# homeboard9.net
KiCad netlist of a schematic drawn in EAGLE
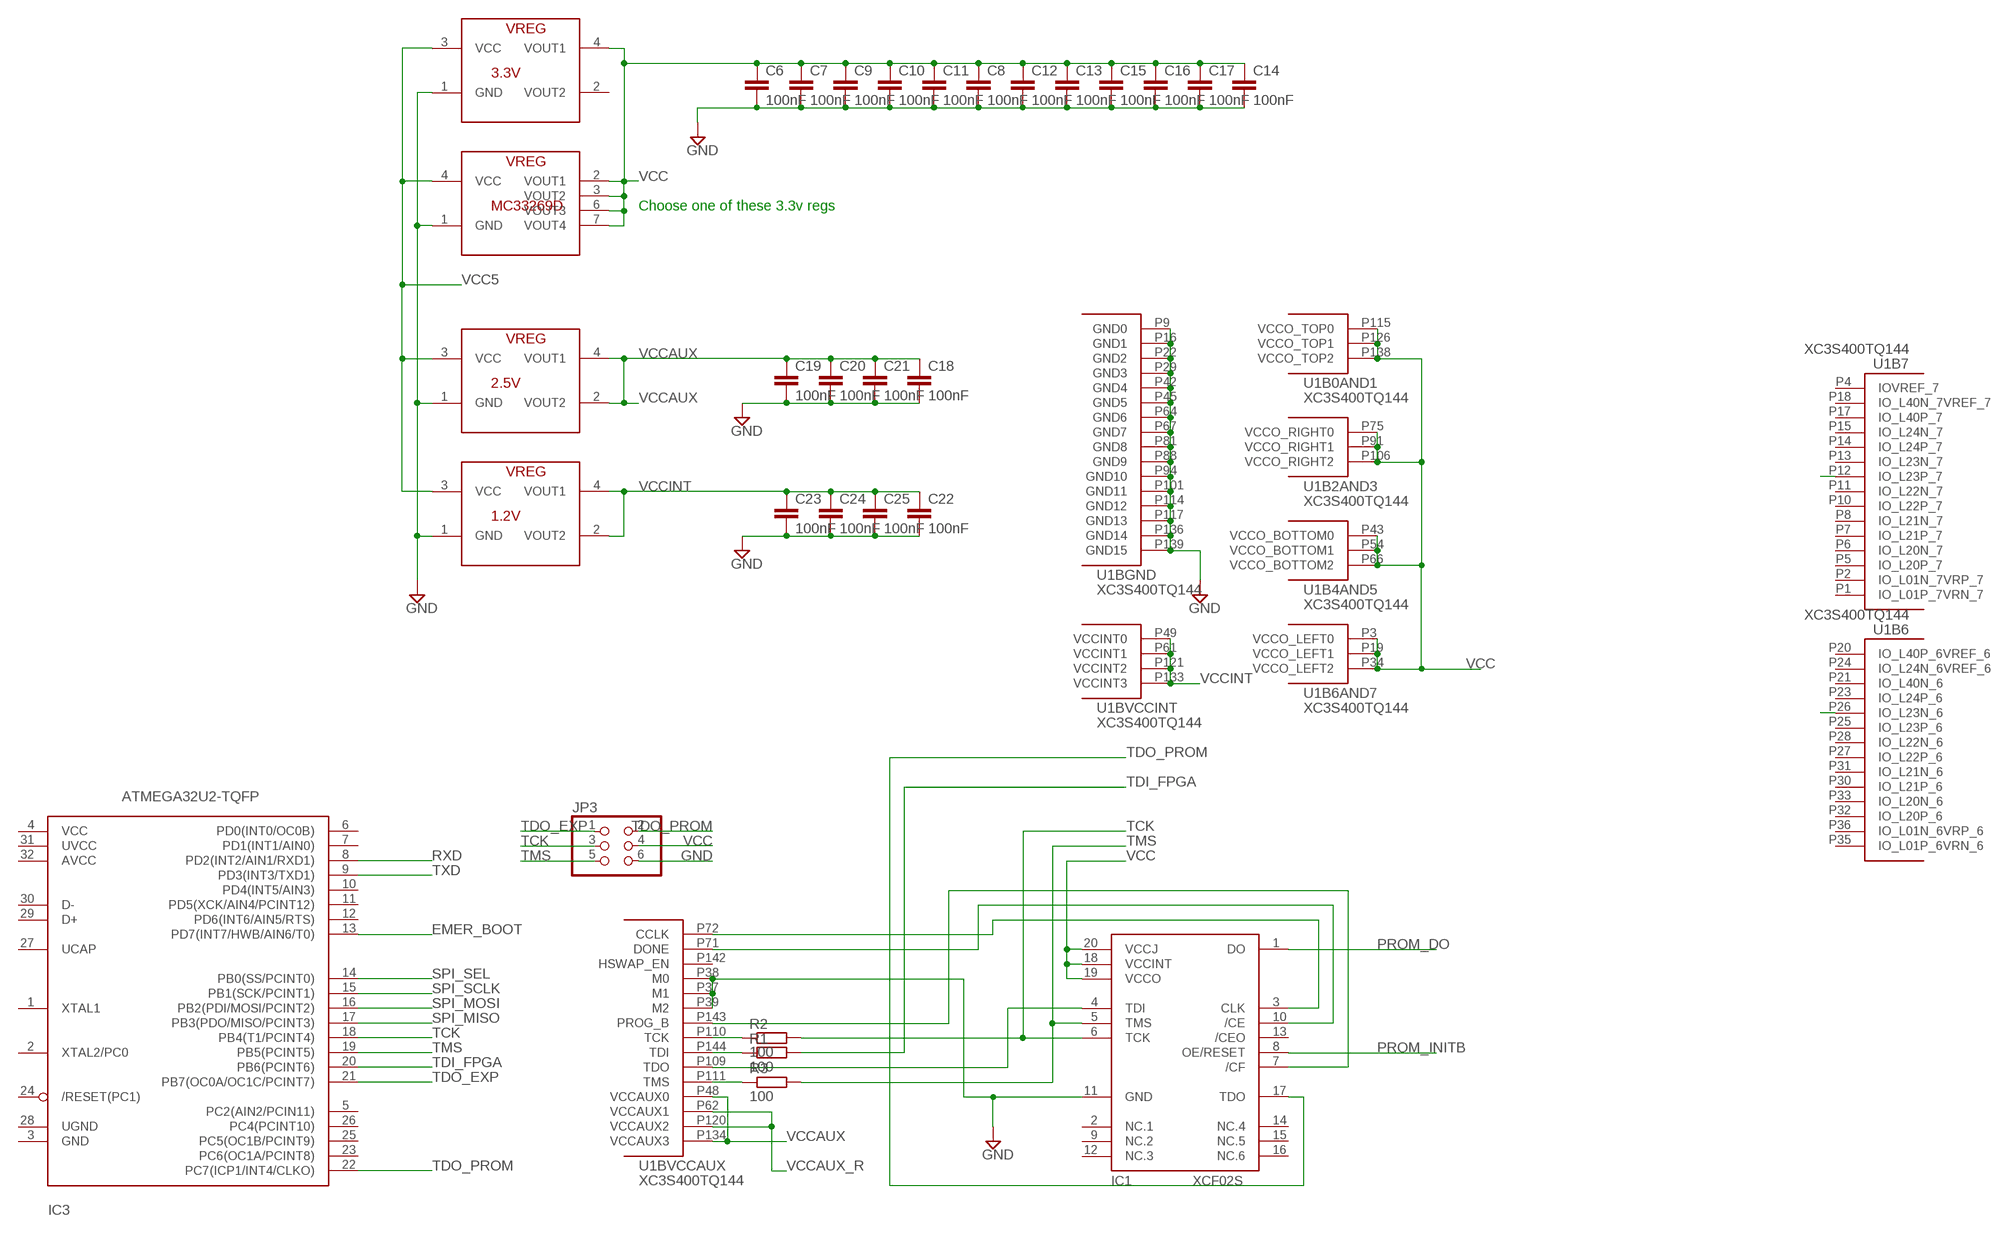
[diagram p0: schematic, sheet 1, part 1 of 3]
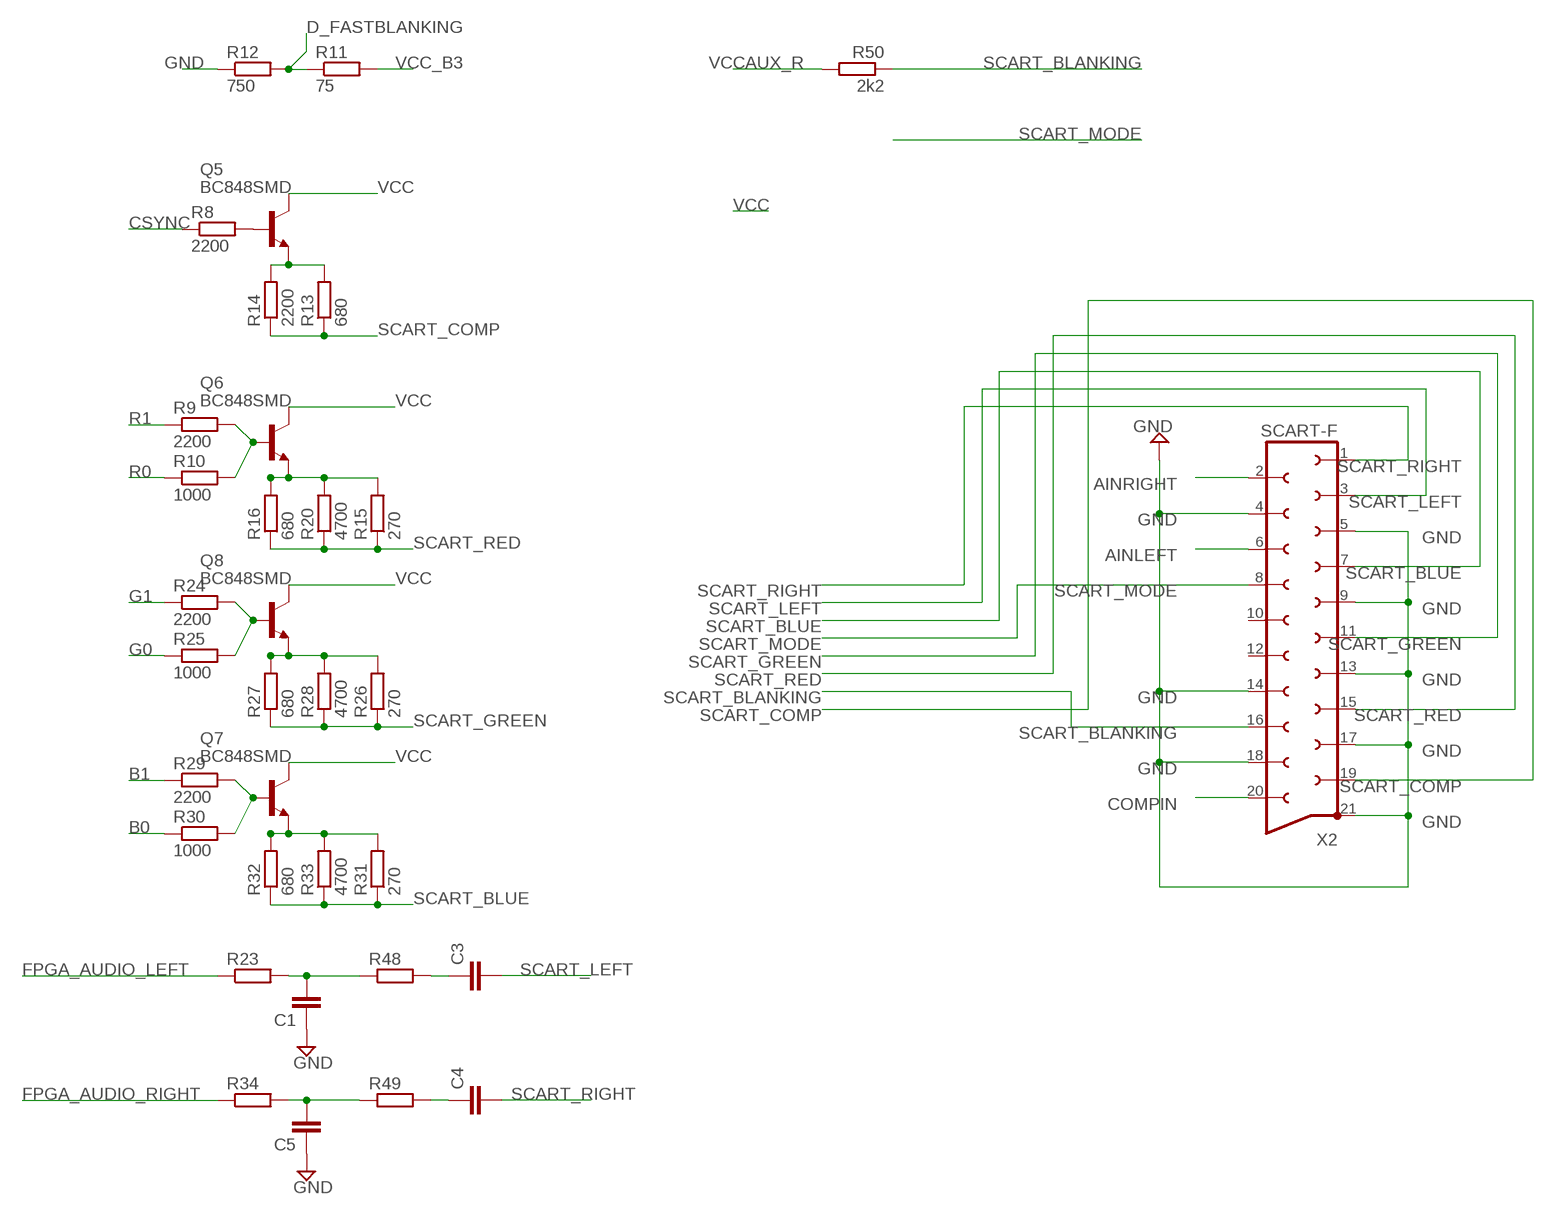
[diagram p1: schematic, sheet 1, part 2 of 3]
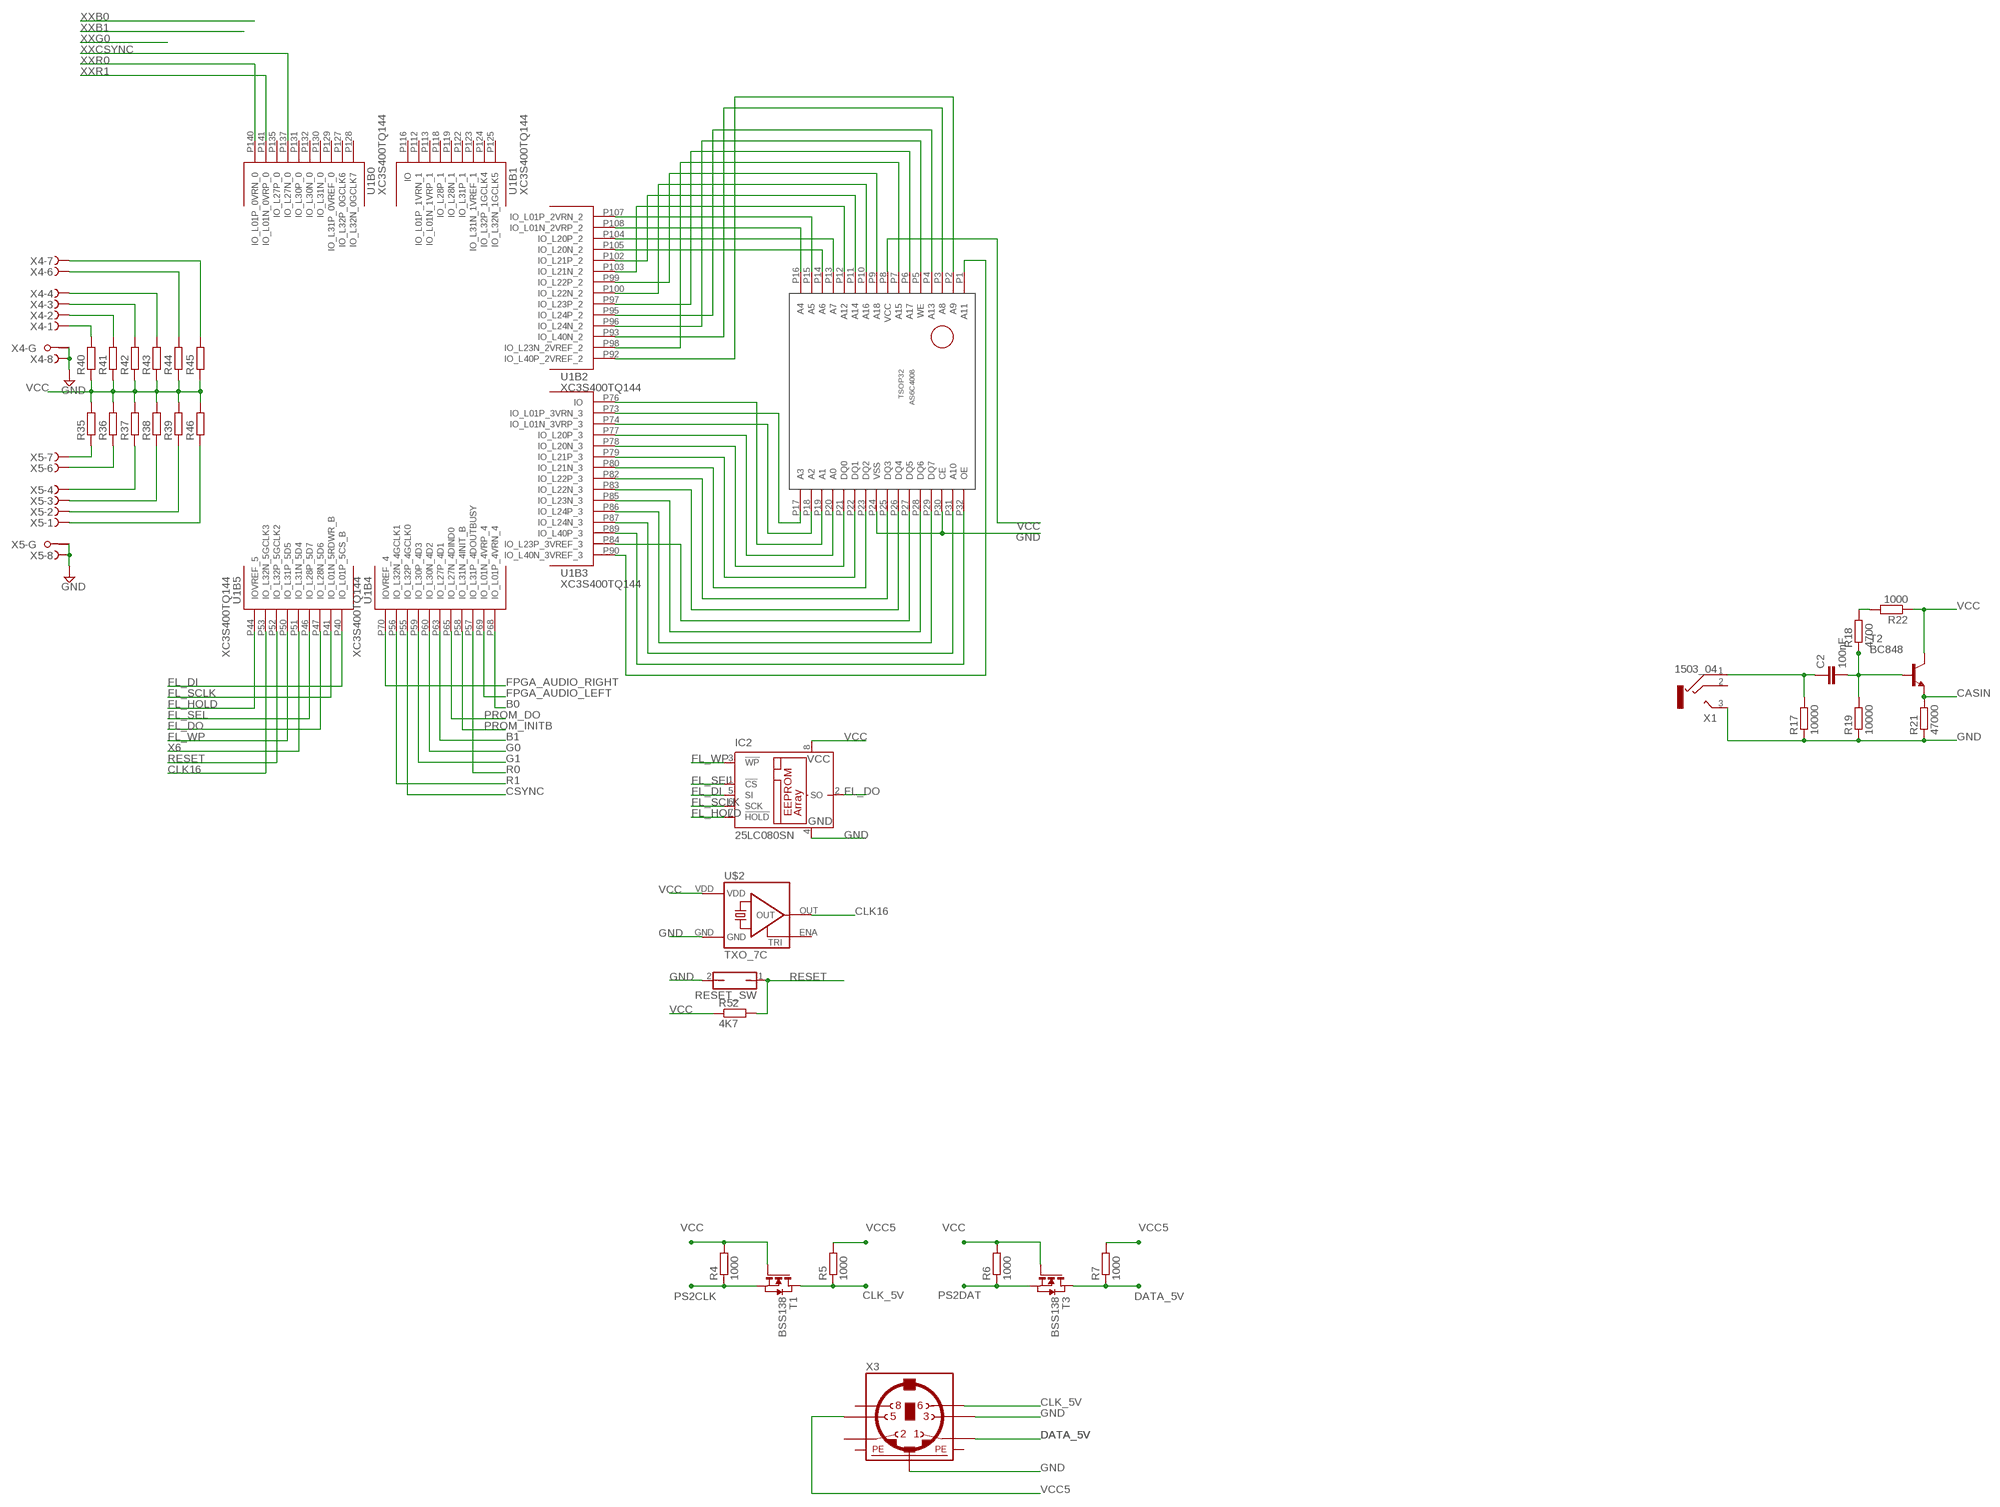
[diagram p2: schematic, sheet 1, part 3 of 3]

(export (version "E")
  (design (tool "Eeschema 10.0.6"))
  (components
    (comp (ref "C1")
      (value "C-EUC0603")
      (footprint "eagle-import:C0603")
      (libsource (lib "eagle-import") (part "resistor_C-EUC0603"))
    )
    (comp (ref "C2")
      (value "100nF")
      (footprint "eagle-import:C0603")
      (libsource (lib "eagle-import") (part "resistor_C-EUC0603"))
    )
    (comp (ref "C3")
      (value "C-EUC0603")
      (footprint "eagle-import:C0603")
      (libsource (lib "eagle-import") (part "resistor_C-EUC0603"))
    )
    (comp (ref "C4")
      (value "C-EUC0603")
      (footprint "eagle-import:C0603")
      (libsource (lib "eagle-import") (part "resistor_C-EUC0603"))
    )
    (comp (ref "C5")
      (value "C-EUC0603")
      (footprint "eagle-import:C0603")
      (libsource (lib "eagle-import") (part "resistor_C-EUC0603"))
    )
    (comp (ref "C6")
      (value "100nF")
      (footprint "eagle-import:C0603")
      (libsource (lib "eagle-import") (part "C-EUC0603"))
    )
    (comp (ref "C7")
      (value "100nF")
      (footprint "eagle-import:C0603")
      (libsource (lib "eagle-import") (part "C-EUC0603"))
    )
    (comp (ref "C8")
      (value "100nF")
      (footprint "eagle-import:C0603")
      (libsource (lib "eagle-import") (part "C-EUC0603"))
    )
    (comp (ref "C9")
      (value "100nF")
      (footprint "eagle-import:C0603")
      (libsource (lib "eagle-import") (part "C-EUC0603"))
    )
    (comp (ref "C10")
      (value "100nF")
      (footprint "eagle-import:C0603")
      (libsource (lib "eagle-import") (part "C-EUC0603"))
    )
    (comp (ref "C11")
      (value "100nF")
      (footprint "eagle-import:C0603")
      (libsource (lib "eagle-import") (part "C-EUC0603"))
    )
    (comp (ref "C12")
      (value "100nF")
      (footprint "eagle-import:C0603")
      (libsource (lib "eagle-import") (part "C-EUC0603"))
    )
    (comp (ref "C13")
      (value "100nF")
      (footprint "eagle-import:C0603")
      (libsource (lib "eagle-import") (part "C-EUC0603"))
    )
    (comp (ref "C14")
      (value "100nF")
      (footprint "eagle-import:C0603")
      (libsource (lib "eagle-import") (part "C-EUC0603"))
    )
    (comp (ref "C15")
      (value "100nF")
      (footprint "eagle-import:C0603")
      (libsource (lib "eagle-import") (part "C-EUC0603"))
    )
    (comp (ref "C16")
      (value "100nF")
      (footprint "eagle-import:C0603")
      (libsource (lib "eagle-import") (part "C-EUC0603"))
    )
    (comp (ref "C17")
      (value "100nF")
      (footprint "eagle-import:C0603")
      (libsource (lib "eagle-import") (part "C-EUC0603"))
    )
    (comp (ref "C18")
      (value "100nF")
      (footprint "eagle-import:C0603")
      (libsource (lib "eagle-import") (part "C-EUC0603"))
    )
    (comp (ref "C19")
      (value "100nF")
      (footprint "eagle-import:C0603")
      (libsource (lib "eagle-import") (part "C-EUC0603"))
    )
    (comp (ref "C20")
      (value "100nF")
      (footprint "eagle-import:C0603")
      (libsource (lib "eagle-import") (part "C-EUC0603"))
    )
    (comp (ref "C21")
      (value "100nF")
      (footprint "eagle-import:C0603")
      (libsource (lib "eagle-import") (part "C-EUC0603"))
    )
    (comp (ref "C22")
      (value "100nF")
      (footprint "eagle-import:C0603")
      (libsource (lib "eagle-import") (part "C-EUC0603"))
    )
    (comp (ref "C23")
      (value "100nF")
      (footprint "eagle-import:C0603")
      (libsource (lib "eagle-import") (part "C-EUC0603"))
    )
    (comp (ref "C24")
      (value "100nF")
      (footprint "eagle-import:C0603")
      (libsource (lib "eagle-import") (part "C-EUC0603"))
    )
    (comp (ref "C25")
      (value "100nF")
      (footprint "eagle-import:C0603")
      (libsource (lib "eagle-import") (part "C-EUC0603"))
    )
    (comp (ref "IC1")
      (value "XCF02S")
      (footprint "eagle-import:VO20")
      (libsource (lib "eagle-import") (part "XCF02S"))
    )
    (comp (ref "IC2")
      (value "25LC080SN")
      (footprint "eagle-import:SO-08")
      (fields (field (name "MF") "MICROCHIP") (field (name "MPN") "25LC080/SN"))
      (libsource (lib "eagle-import") (part "25SNLC080"))
    )
    (comp (ref "IC3")
      (value "ATMEGA32U2-TQFP")
      (footprint "eagle-import:TQFP32-08")
      (libsource (lib "eagle-import") (part "ATMEGA32U2-TQFP"))
    )
    (comp (ref "JP3")
      (value "PINHD-2X3")
      (footprint "eagle-import:2X03")
      (libsource (lib "eagle-import") (part "PINHD-2X3"))
    )
    (comp (ref "Q5")
      (value "BC848SMD")
      (footprint "eagle-import:SOT23")
      (libsource (lib "eagle-import") (part "BC848SMD"))
    )
    (comp (ref "Q6")
      (value "BC848SMD")
      (footprint "eagle-import:SOT23")
      (libsource (lib "eagle-import") (part "BC848SMD"))
    )
    (comp (ref "Q7")
      (value "BC848SMD")
      (footprint "eagle-import:SOT23")
      (libsource (lib "eagle-import") (part "BC848SMD"))
    )
    (comp (ref "Q8")
      (value "BC848SMD")
      (footprint "eagle-import:SOT23")
      (libsource (lib "eagle-import") (part "BC848SMD"))
    )
    (comp (ref "R1")
      (value "100")
      (footprint "eagle-import:R0805")
      (libsource (lib "eagle-import") (part "R-EU_R0805"))
    )
    (comp (ref "R2")
      (value "100")
      (footprint "eagle-import:R0805")
      (libsource (lib "eagle-import") (part "R-EU_R0805"))
    )
    (comp (ref "R3")
      (value "100")
      (footprint "eagle-import:R0805")
      (libsource (lib "eagle-import") (part "R-EU_R0805"))
    )
    (comp (ref "R4")
      (value "1000")
      (footprint "eagle-import:R0805")
      (libsource (lib "eagle-import") (part "R-EU_R0805"))
    )
    (comp (ref "R5")
      (value "1000")
      (footprint "eagle-import:R0805")
      (libsource (lib "eagle-import") (part "R-EU_R0805"))
    )
    (comp (ref "R6")
      (value "1000")
      (footprint "eagle-import:R0805")
      (libsource (lib "eagle-import") (part "R-EU_R0805"))
    )
    (comp (ref "R7")
      (value "1000")
      (footprint "eagle-import:R0805")
      (libsource (lib "eagle-import") (part "R-EU_R0805"))
    )
    (comp (ref "R8")
      (value "2200")
      (footprint "eagle-import:R0805")
      (libsource (lib "eagle-import") (part "R-EU_R0805"))
    )
    (comp (ref "R9")
      (value "2200")
      (footprint "eagle-import:R0805")
      (libsource (lib "eagle-import") (part "R-EU_R0805"))
    )
    (comp (ref "R10")
      (value "1000")
      (footprint "eagle-import:R0805")
      (libsource (lib "eagle-import") (part "R-EU_R0805"))
    )
    (comp (ref "R11")
      (value "75")
      (footprint "eagle-import:R0805")
      (libsource (lib "eagle-import") (part "R-EU_R0805"))
    )
    (comp (ref "R12")
      (value "750")
      (footprint "eagle-import:R0805")
      (libsource (lib "eagle-import") (part "R-EU_R0805"))
    )
    (comp (ref "R13")
      (value "680")
      (footprint "eagle-import:R0805")
      (libsource (lib "eagle-import") (part "R-EU_R0805"))
    )
    (comp (ref "R14")
      (value "2200")
      (footprint "eagle-import:R0805")
      (libsource (lib "eagle-import") (part "R-EU_R0805"))
    )
    (comp (ref "R15")
      (value "270")
      (footprint "eagle-import:R0805")
      (libsource (lib "eagle-import") (part "R-EU_R0805"))
    )
    (comp (ref "R16")
      (value "680")
      (footprint "eagle-import:R0805")
      (libsource (lib "eagle-import") (part "R-EU_R0805"))
    )
    (comp (ref "R17")
      (value "10000")
      (footprint "eagle-import:R0805")
      (libsource (lib "eagle-import") (part "R-EU_R0805"))
    )
    (comp (ref "R18")
      (value "4700")
      (footprint "eagle-import:R0805")
      (libsource (lib "eagle-import") (part "R-EU_R0805"))
    )
    (comp (ref "R19")
      (value "10000")
      (footprint "eagle-import:R0805")
      (libsource (lib "eagle-import") (part "R-EU_R0805"))
    )
    (comp (ref "R20")
      (value "4700")
      (footprint "eagle-import:R0805")
      (libsource (lib "eagle-import") (part "R-EU_R0805"))
    )
    (comp (ref "R21")
      (value "47000")
      (footprint "eagle-import:R0805")
      (libsource (lib "eagle-import") (part "R-EU_R0805"))
    )
    (comp (ref "R22")
      (value "1000")
      (footprint "eagle-import:R0805")
      (libsource (lib "eagle-import") (part "R-EU_R0805"))
    )
    (comp (ref "R23")
      (value "R-EU_M0805")
      (footprint "eagle-import:M0805")
      (libsource (lib "eagle-import") (part "resistor_R-EU_M0805"))
    )
    (comp (ref "R24")
      (value "2200")
      (footprint "eagle-import:R0805")
      (libsource (lib "eagle-import") (part "R-EU_R0805"))
    )
    (comp (ref "R25")
      (value "1000")
      (footprint "eagle-import:R0805")
      (libsource (lib "eagle-import") (part "R-EU_R0805"))
    )
    (comp (ref "R26")
      (value "270")
      (footprint "eagle-import:R0805")
      (libsource (lib "eagle-import") (part "R-EU_R0805"))
    )
    (comp (ref "R27")
      (value "680")
      (footprint "eagle-import:R0805")
      (libsource (lib "eagle-import") (part "R-EU_R0805"))
    )
    (comp (ref "R28")
      (value "4700")
      (footprint "eagle-import:R0805")
      (libsource (lib "eagle-import") (part "R-EU_R0805"))
    )
    (comp (ref "R29")
      (value "2200")
      (footprint "eagle-import:R0805")
      (libsource (lib "eagle-import") (part "R-EU_R0805"))
    )
    (comp (ref "R30")
      (value "1000")
      (footprint "eagle-import:R0805")
      (libsource (lib "eagle-import") (part "R-EU_R0805"))
    )
    (comp (ref "R31")
      (value "270")
      (footprint "eagle-import:R0805")
      (libsource (lib "eagle-import") (part "R-EU_R0805"))
    )
    (comp (ref "R32")
      (value "680")
      (footprint "eagle-import:R0805")
      (libsource (lib "eagle-import") (part "R-EU_R0805"))
    )
    (comp (ref "R33")
      (value "4700")
      (footprint "eagle-import:R0805")
      (libsource (lib "eagle-import") (part "R-EU_R0805"))
    )
    (comp (ref "R34")
      (value "R-EU_M0805")
      (footprint "eagle-import:M0805")
      (libsource (lib "eagle-import") (part "resistor_R-EU_M0805"))
    )
    (comp (ref "R35")
      (value "R-EU_M0805")
      (footprint "eagle-import:M0805")
      (libsource (lib "eagle-import") (part "resistor_R-EU_M0805"))
    )
    (comp (ref "R36")
      (value "R-EU_M0805")
      (footprint "eagle-import:M0805")
      (libsource (lib "eagle-import") (part "resistor_R-EU_M0805"))
    )
    (comp (ref "R37")
      (value "R-EU_M0805")
      (footprint "eagle-import:M0805")
      (libsource (lib "eagle-import") (part "resistor_R-EU_M0805"))
    )
    (comp (ref "R38")
      (value "R-EU_M0805")
      (footprint "eagle-import:M0805")
      (libsource (lib "eagle-import") (part "resistor_R-EU_M0805"))
    )
    (comp (ref "R39")
      (value "R-EU_M0805")
      (footprint "eagle-import:M0805")
      (libsource (lib "eagle-import") (part "resistor_R-EU_M0805"))
    )
    (comp (ref "R40")
      (value "R-EU_M0805")
      (footprint "eagle-import:M0805")
      (libsource (lib "eagle-import") (part "resistor_R-EU_M0805"))
    )
    (comp (ref "R41")
      (value "R-EU_M0805")
      (footprint "eagle-import:M0805")
      (libsource (lib "eagle-import") (part "resistor_R-EU_M0805"))
    )
    (comp (ref "R42")
      (value "R-EU_M0805")
      (footprint "eagle-import:M0805")
      (libsource (lib "eagle-import") (part "resistor_R-EU_M0805"))
    )
    (comp (ref "R43")
      (value "R-EU_M0805")
      (footprint "eagle-import:M0805")
      (libsource (lib "eagle-import") (part "resistor_R-EU_M0805"))
    )
    (comp (ref "R44")
      (value "R-EU_M0805")
      (footprint "eagle-import:M0805")
      (libsource (lib "eagle-import") (part "resistor_R-EU_M0805"))
    )
    (comp (ref "R45")
      (value "R-EU_M0805")
      (footprint "eagle-import:M0805")
      (libsource (lib "eagle-import") (part "resistor_R-EU_M0805"))
    )
    (comp (ref "R46")
      (value "R-EU_M0805")
      (footprint "eagle-import:M0805")
      (libsource (lib "eagle-import") (part "resistor_R-EU_M0805"))
    )
    (comp (ref "R48")
      (value "R-EU_M0805")
      (footprint "eagle-import:M0805")
      (libsource (lib "eagle-import") (part "resistor_R-EU_M0805"))
    )
    (comp (ref "R49")
      (value "R-EU_M0805")
      (footprint "eagle-import:M0805")
      (libsource (lib "eagle-import") (part "resistor_R-EU_M0805"))
    )
    (comp (ref "R50")
      (value "2k2")
      (footprint "eagle-import:M0805")
      (libsource (lib "eagle-import") (part "resistor_R-EU_M0805"))
    )
    (comp (ref "R52")
      (value "4K7")
      (footprint "eagle-import:M0805")
      (libsource (lib "eagle-import") (part "resistor_R-EU_M0805"))
    )
    (comp (ref "REG1.2")
      (value "1.2V")
      (footprint "eagle-import:SOT223")
      (libsource (lib "eagle-import") (part "NX1117"))
    )
    (comp (ref "REG2.5")
      (value "2.5V")
      (footprint "eagle-import:SOT223")
      (libsource (lib "eagle-import") (part "NX1117"))
    )
    (comp (ref "RESET_SW")
      (value "JP1Q")
      (footprint "eagle-import:JP1")
      (libsource (lib "eagle-import") (part "JP1Q"))
    )
    (comp (ref "T1")
      (value "BSS138")
      (footprint "eagle-import:SOT-23")
      (libsource (lib "eagle-import") (part "NMOSSOT23"))
    )
    (comp (ref "T2")
      (value "BC848")
      (footprint "eagle-import:SOT23")
      (libsource (lib "eagle-import") (part "BC848"))
    )
    (comp (ref "T3")
      (value "BSS138")
      (footprint "eagle-import:SOT-23")
      (libsource (lib "eagle-import") (part "NMOSSOT23"))
    )
    (comp (ref "U$1")
      (value "AS6C4008")
      (footprint "eagle-import:TSOP32")
      (libsource (lib "eagle-import") (part "AS6C4008"))
    )
    (comp (ref "U$2")
      (value "TXO_7C")
      (footprint "eagle-import:OSC_7C")
      (libsource (lib "eagle-import") (part "TXO_7C"))
    )
    (comp (ref "U$3")
      (value "MC33269D")
      (footprint "eagle-import:SO8")
      (libsource (lib "eagle-import") (part "MC33269D"))
    )
    (comp (ref "U$4")
      (value "3.3V")
      (footprint "eagle-import:SOT223")
      (libsource (lib "eagle-import") (part "NX1117"))
    )
    (comp (ref "U1")
      (value "XC3S400TQ144")
      (footprint "eagle-import:TQ144")
      (libsource (lib "eagle-import") (part "XC3S400TQ144"))
    )
    (comp (ref "X1")
      (value "1503_04")
      (footprint "eagle-import:1503_04")
      (libsource (lib "eagle-import") (part "1503_04"))
    )
    (comp (ref "X2")
      (value "SCART-F")
      (footprint "eagle-import:SCART-F")
      (libsource (lib "eagle-import") (part "SCART-F"))
    )
    (comp (ref "X3")
      (value "MINI_DIN_6")
      (footprint "eagle-import:M_DIN6")
      (libsource (lib "eagle-import") (part "MINI_DIN_6"))
    )
    (comp (ref "X4")
      (value "F09HPS")
      (footprint "eagle-import:F09HP")
      (libsource (lib "eagle-import") (part "F09HPS"))
    )
    (comp (ref "X5")
      (value "F09HPS")
      (footprint "eagle-import:F09HP")
      (libsource (lib "eagle-import") (part "F09HPS"))
    )
  )
  (nets
    (net (code "1") (name "/AINLEFT") (class "Default")
      (node (ref "X2") (pin "6") (pinfunction "6_6") (pintype "passive"))
    )
    (net (code "2") (name "/AINRIGHT") (class "Default")
      (node (ref "X2") (pin "2") (pinfunction "2_2") (pintype "passive"))
    )
    (net (code "3") (name "/B0") (class "Default")
      (node (ref "R30") (pin "1") (pinfunction "1_1") (pintype "passive"))
      (node (ref "U1") (pin "P68") (pinfunction "IO_L01P_4VRN_4_P68") (pintype "bidirectional"))
    )
    (net (code "4") (name "/B1") (class "Default")
      (node (ref "R29") (pin "1") (pinfunction "1_1") (pintype "passive"))
      (node (ref "U1") (pin "P63") (pinfunction "IO_L27P_4D1_P63") (pintype "bidirectional"))
    )
    (net (code "5") (name "/CASIN") (class "Default")
      (node (ref "R21") (pin "2") (pinfunction "2_2") (pintype "passive"))
      (node (ref "T2") (pin "2") (pinfunction "E_2") (pintype "passive"))
    )
    (net (code "6") (name "/CLK16") (class "Default")
      (node (ref "U$2") (pin "OUT") (pinfunction "OUT_OUT") (pintype "output"))
      (node (ref "U1") (pin "P53") (pinfunction "IO_L32N_5GCLK3_P53") (pintype "bidirectional"))
    )
    (net (code "7") (name "/CLK_5V") (class "Default")
      (node (ref "R5") (pin "1") (pinfunction "1_1") (pintype "passive"))
      (node (ref "T1") (pin "1") (pinfunction "D_1") (pintype "passive"))
      (node (ref "X3") (pin "6") (pinfunction "6_6") (pintype "passive"))
    )
    (net (code "8") (name "/COMPIN") (class "Default")
      (node (ref "X2") (pin "20") (pinfunction "20_20") (pintype "passive"))
    )
    (net (code "9") (name "/CSYNC") (class "Default")
      (node (ref "R8") (pin "1") (pinfunction "1_1") (pintype "passive"))
      (node (ref "U1") (pin "P55") (pinfunction "IO_L32P_4GCLK0_P55") (pintype "bidirectional"))
    )
    (net (code "10") (name "/DATA_5V") (class "Default")
      (node (ref "R7") (pin "1") (pinfunction "1_1") (pintype "passive"))
      (node (ref "T3") (pin "1") (pinfunction "D_1") (pintype "passive"))
      (node (ref "X3") (pin "1") (pinfunction "1_1") (pintype "passive"))
    )
    (net (code "11") (name "/D_FASTBLANKING") (class "Default")
      (node (ref "R11") (pin "1") (pinfunction "1_1") (pintype "passive"))
      (node (ref "R12") (pin "2") (pinfunction "2_2") (pintype "passive"))
    )
    (net (code "12") (name "/EMER_BOOT") (class "Default")
      (node (ref "IC3") (pin "13") (pinfunction "PD7(INT7/HWB/AIN6/T0)_13") (pintype "bidirectional"))
    )
    (net (code "13") (name "/FL_DI") (class "Default")
      (node (ref "IC2") (pin "5") (pinfunction "SI_5") (pintype "input"))
      (node (ref "U1") (pin "P40") (pinfunction "IO_L01P_5CS_B_P40") (pintype "bidirectional"))
    )
    (net (code "14") (name "/FL_DO") (class "Default")
      (node (ref "IC2") (pin "2") (pinfunction "SO_2") (pintype "bidirectional"))
      (node (ref "U1") (pin "P47") (pinfunction "IO_L28N_5D6_P47") (pintype "bidirectional"))
    )
    (net (code "15") (name "/FL_HOLD") (class "Default")
      (node (ref "IC2") (pin "7") (pinfunction "~{HOLD}_7") (pintype "input"))
      (node (ref "U1") (pin "P44") (pinfunction "IOVREF_5_P44") (pintype "bidirectional"))
    )
    (net (code "16") (name "/FL_SCLK") (class "Default")
      (node (ref "IC2") (pin "6") (pinfunction "SCK_6") (pintype "input"))
      (node (ref "U1") (pin "P41") (pinfunction "IO_L01N_5RDWR_B_P41") (pintype "bidirectional"))
    )
    (net (code "17") (name "/FL_SEL") (class "Default")
      (node (ref "IC2") (pin "1") (pinfunction "~{CS}_1") (pintype "input"))
      (node (ref "U1") (pin "P46") (pinfunction "IO_L28P_5D7_P46") (pintype "bidirectional"))
    )
    (net (code "18") (name "/FL_WP") (class "Default")
      (node (ref "IC2") (pin "3") (pinfunction "~{WP}_3") (pintype "input"))
      (node (ref "U1") (pin "P50") (pinfunction "IO_L31P_5D5_P50") (pintype "bidirectional"))
    )
    (net (code "19") (name "/FPGA_AUDIO_LEFT") (class "Default")
      (node (ref "R23") (pin "1") (pinfunction "1_1") (pintype "passive"))
      (node (ref "U1") (pin "P69") (pinfunction "IO_L01N_4VRP_4_P69") (pintype "bidirectional"))
    )
    (net (code "20") (name "/FPGA_AUDIO_RIGHT") (class "Default")
      (node (ref "R34") (pin "1") (pinfunction "1_1") (pintype "passive"))
      (node (ref "U1") (pin "P70") (pinfunction "IOVREF_4_P70") (pintype "bidirectional"))
    )
    (net (code "21") (name "/G0") (class "Default")
      (node (ref "R25") (pin "1") (pinfunction "1_1") (pintype "passive"))
      (node (ref "U1") (pin "P60") (pinfunction "IO_L30N_4D2_P60") (pintype "bidirectional"))
    )
    (net (code "22") (name "/G1") (class "Default")
      (node (ref "R24") (pin "1") (pinfunction "1_1") (pintype "passive"))
      (node (ref "U1") (pin "P59") (pinfunction "IO_L30P_4D3_P59") (pintype "bidirectional"))
    )
    (net (code "23") (name "/PE1") (class "Default")
      (node (ref "X3") (pin "SH1") (pinfunction "PE1_SH1") (pintype "power_in"))
    )
    (net (code "24") (name "/PE3") (class "Default")
      (node (ref "X3") (pin "SH3") (pinfunction "PE3_SH3") (pintype "power_in"))
    )
    (net (code "25") (name "/PROM_DO") (class "Default")
      (node (ref "IC1") (pin "1") (pinfunction "DO_1") (pintype "bidirectional"))
      (node (ref "U1") (pin "P65") (pinfunction "IO_L27N_4DIND0_P65") (pintype "bidirectional"))
    )
    (net (code "26") (name "/PROM_INITB") (class "Default")
      (node (ref "IC1") (pin "8") (pinfunction "OE/RESET_8") (pintype "bidirectional"))
      (node (ref "U1") (pin "P58") (pinfunction "IO_L31N_4INIT_B_P58") (pintype "bidirectional"))
    )
    (net (code "27") (name "/PS2CLK") (class "Default")
      (node (ref "R4") (pin "1") (pinfunction "1_1") (pintype "passive"))
      (node (ref "T1") (pin "2") (pinfunction "S_2") (pintype "passive"))
    )
    (net (code "28") (name "/PS2DAT") (class "Default")
      (node (ref "R6") (pin "1") (pinfunction "1_1") (pintype "passive"))
      (node (ref "T3") (pin "2") (pinfunction "S_2") (pintype "passive"))
    )
    (net (code "29") (name "/R0") (class "Default")
      (node (ref "R10") (pin "1") (pinfunction "1_1") (pintype "passive"))
      (node (ref "U1") (pin "P57") (pinfunction "IO_L31P_4DOUTBUSY_P57") (pintype "bidirectional"))
    )
    (net (code "30") (name "/R1") (class "Default")
      (node (ref "R9") (pin "1") (pinfunction "1_1") (pintype "passive"))
      (node (ref "U1") (pin "P56") (pinfunction "IO_L32N_4GCLK1_P56") (pintype "bidirectional"))
    )
    (net (code "31") (name "/RESET") (class "Default")
      (node (ref "R52") (pin "2") (pinfunction "2_2") (pintype "passive"))
      (node (ref "RESET_SW") (pin "1") (pinfunction "1_1") (pintype "passive"))
      (node (ref "U1") (pin "P52") (pinfunction "IO_L32P_5GCLK2_P52") (pintype "bidirectional"))
    )
    (net (code "32") (name "/RXD") (class "Default")
      (node (ref "IC3") (pin "8") (pinfunction "PD2(INT2/AIN1/RXD1)_8") (pintype "bidirectional"))
    )
    (net (code "33") (name "/SCART_BLANKING") (class "Default")
      (node (ref "R50") (pin "1") (pinfunction "1_1") (pintype "passive"))
      (node (ref "X2") (pin "16") (pinfunction "16_16") (pintype "passive"))
    )
    (net (code "34") (name "/SCART_BLUE") (class "Default")
      (node (ref "R31") (pin "1") (pinfunction "1_1") (pintype "passive"))
      (node (ref "R32") (pin "1") (pinfunction "1_1") (pintype "passive"))
      (node (ref "R33") (pin "1") (pinfunction "1_1") (pintype "passive"))
      (node (ref "X2") (pin "7") (pinfunction "7_7") (pintype "passive"))
    )
    (net (code "35") (name "/SCART_COMP") (class "Default")
      (node (ref "R13") (pin "1") (pinfunction "1_1") (pintype "passive"))
      (node (ref "R14") (pin "1") (pinfunction "1_1") (pintype "passive"))
      (node (ref "X2") (pin "19") (pinfunction "19_19") (pintype "passive"))
    )
    (net (code "36") (name "/SCART_GREEN") (class "Default")
      (node (ref "R26") (pin "1") (pinfunction "1_1") (pintype "passive"))
      (node (ref "R27") (pin "1") (pinfunction "1_1") (pintype "passive"))
      (node (ref "R28") (pin "1") (pinfunction "1_1") (pintype "passive"))
      (node (ref "X2") (pin "11") (pinfunction "11_11") (pintype "passive"))
    )
    (net (code "37") (name "/SCART_LEFT") (class "Default")
      (node (ref "C3") (pin "2") (pinfunction "2_2") (pintype "passive"))
      (node (ref "X2") (pin "3") (pinfunction "3_3") (pintype "passive"))
    )
    (net (code "38") (name "/SCART_MODE") (class "Default")
      (node (ref "X2") (pin "8") (pinfunction "8_8") (pintype "passive"))
    )
    (net (code "39") (name "/SCART_RED") (class "Default")
      (node (ref "R15") (pin "1") (pinfunction "1_1") (pintype "passive"))
      (node (ref "R16") (pin "1") (pinfunction "1_1") (pintype "passive"))
      (node (ref "R20") (pin "1") (pinfunction "1_1") (pintype "passive"))
      (node (ref "X2") (pin "15") (pinfunction "15_15") (pintype "passive"))
    )
    (net (code "40") (name "/SCART_RIGHT") (class "Default")
      (node (ref "C4") (pin "2") (pinfunction "2_2") (pintype "passive"))
      (node (ref "X2") (pin "1") (pinfunction "1_1") (pintype "passive"))
    )
    (net (code "41") (name "/SPI_MISO") (class "Default")
      (node (ref "IC3") (pin "17") (pinfunction "PB3(PDO/MISO/PCINT3)_17") (pintype "bidirectional"))
    )
    (net (code "42") (name "/SPI_MOSI") (class "Default")
      (node (ref "IC3") (pin "16") (pinfunction "PB2(PDI/MOSI/PCINT2)_16") (pintype "bidirectional"))
    )
    (net (code "43") (name "/SPI_SCLK") (class "Default")
      (node (ref "IC3") (pin "15") (pinfunction "PB1(SCK/PCINT1)_15") (pintype "bidirectional"))
    )
    (net (code "44") (name "/SPI_SEL") (class "Default")
      (node (ref "IC3") (pin "14") (pinfunction "PB0(SS/PCINT0)_14") (pintype "bidirectional"))
    )
    (net (code "45") (name "/TCK") (class "Default")
      (node (ref "IC1") (pin "6") (pinfunction "TCK_6") (pintype "bidirectional"))
      (node (ref "IC3") (pin "18") (pinfunction "PB4(T1/PCINT4)_18") (pintype "bidirectional"))
      (node (ref "JP3") (pin "3") (pinfunction "3_3") (pintype "passive"))
      (node (ref "R2") (pin "2") (pinfunction "2_2") (pintype "passive"))
    )
    (net (code "46") (name "/TDI_FPGA") (class "Default")
      (node (ref "IC3") (pin "20") (pinfunction "PB6(PCINT6)_20") (pintype "bidirectional"))
      (node (ref "R1") (pin "2") (pinfunction "2_2") (pintype "passive"))
    )
    (net (code "47") (name "/TDO_EXP") (class "Default")
      (node (ref "IC3") (pin "21") (pinfunction "PB7(OC0A/OC1C/PCINT7)_21") (pintype "bidirectional"))
      (node (ref "JP3") (pin "1") (pinfunction "1_1") (pintype "passive"))
    )
    (net (code "48") (name "/TDO_PROM") (class "Default")
      (node (ref "IC1") (pin "17") (pinfunction "TDO_17") (pintype "bidirectional"))
      (node (ref "IC3") (pin "22") (pinfunction "PC7(ICP1/INT4/CLKO)_22") (pintype "bidirectional"))
      (node (ref "JP3") (pin "2") (pinfunction "2_2") (pintype "passive"))
    )
    (net (code "49") (name "/TMS") (class "Default")
      (node (ref "IC1") (pin "5") (pinfunction "TMS_5") (pintype "bidirectional"))
      (node (ref "IC3") (pin "19") (pinfunction "PB5(PCINT5)_19") (pintype "bidirectional"))
      (node (ref "JP3") (pin "5") (pinfunction "5_5") (pintype "passive"))
      (node (ref "R3") (pin "2") (pinfunction "2_2") (pintype "passive"))
    )
    (net (code "50") (name "/TXD") (class "Default")
      (node (ref "IC3") (pin "9") (pinfunction "PD3(INT3/TXD1)_9") (pintype "bidirectional"))
    )
    (net (code "51") (name "/VCC") (class "Default")
      (node (ref "C10") (pin "1") (pinfunction "1_1") (pintype "passive"))
      (node (ref "C11") (pin "1") (pinfunction "1_1") (pintype "passive"))
      (node (ref "C12") (pin "1") (pinfunction "1_1") (pintype "passive"))
      (node (ref "C13") (pin "1") (pinfunction "1_1") (pintype "passive"))
      (node (ref "C14") (pin "1") (pinfunction "1_1") (pintype "passive"))
      (node (ref "C15") (pin "1") (pinfunction "1_1") (pintype "passive"))
      (node (ref "C16") (pin "1") (pinfunction "1_1") (pintype "passive"))
      (node (ref "C17") (pin "1") (pinfunction "1_1") (pintype "passive"))
      (node (ref "C6") (pin "1") (pinfunction "1_1") (pintype "passive"))
      (node (ref "C7") (pin "1") (pinfunction "1_1") (pintype "passive"))
      (node (ref "C8") (pin "1") (pinfunction "1_1") (pintype "passive"))
      (node (ref "C9") (pin "1") (pinfunction "1_1") (pintype "passive"))
      (node (ref "IC1") (pin "18") (pinfunction "VCCINT_18") (pintype "bidirectional"))
      (node (ref "IC1") (pin "19") (pinfunction "VCCO_19") (pintype "bidirectional"))
      (node (ref "IC1") (pin "20") (pinfunction "VCCJ_20") (pintype "bidirectional"))
      (node (ref "IC2") (pin "8") (pinfunction "VCC_8") (pintype "power_in"))
      (node (ref "JP3") (pin "4") (pinfunction "4_4") (pintype "passive"))
      (node (ref "Q5") (pin "3") (pinfunction "C_3") (pintype "passive"))
      (node (ref "Q6") (pin "3") (pinfunction "C_3") (pintype "passive"))
      (node (ref "Q7") (pin "3") (pinfunction "C_3") (pintype "passive"))
      (node (ref "Q8") (pin "3") (pinfunction "C_3") (pintype "passive"))
      (node (ref "R22") (pin "1") (pinfunction "1_1") (pintype "passive"))
      (node (ref "R35") (pin "2") (pinfunction "2_2") (pintype "passive"))
      (node (ref "R36") (pin "2") (pinfunction "2_2") (pintype "passive"))
      (node (ref "R37") (pin "2") (pinfunction "2_2") (pintype "passive"))
      (node (ref "R38") (pin "2") (pinfunction "2_2") (pintype "passive"))
      (node (ref "R39") (pin "2") (pinfunction "2_2") (pintype "passive"))
      (node (ref "R4") (pin "2") (pinfunction "2_2") (pintype "passive"))
      (node (ref "R40") (pin "1") (pinfunction "1_1") (pintype "passive"))
      (node (ref "R41") (pin "1") (pinfunction "1_1") (pintype "passive"))
      (node (ref "R42") (pin "1") (pinfunction "1_1") (pintype "passive"))
      (node (ref "R43") (pin "1") (pinfunction "1_1") (pintype "passive"))
      (node (ref "R44") (pin "1") (pinfunction "1_1") (pintype "passive"))
      (node (ref "R45") (pin "1") (pinfunction "1_1") (pintype "passive"))
      (node (ref "R46") (pin "2") (pinfunction "2_2") (pintype "passive"))
      (node (ref "R52") (pin "1") (pinfunction "1_1") (pintype "passive"))
      (node (ref "R6") (pin "2") (pinfunction "2_2") (pintype "passive"))
      (node (ref "T1") (pin "3") (pinfunction "G_3") (pintype "passive"))
      (node (ref "T2") (pin "3") (pinfunction "C_3") (pintype "passive"))
      (node (ref "T3") (pin "3") (pinfunction "G_3") (pintype "passive"))
      (node (ref "U$1") (pin "P8") (pinfunction "VCC_P8") (pintype "bidirectional"))
      (node (ref "U$2") (pin "VDD") (pinfunction "VDD_VDD") (pintype "power_in"))
      (node (ref "U$3") (pin "2") (pinfunction "VOUT1_2") (pintype "output"))
      (node (ref "U$3") (pin "3") (pinfunction "VOUT2_3") (pintype "output"))
      (node (ref "U$3") (pin "6") (pinfunction "VOUT3_6") (pintype "output"))
      (node (ref "U$3") (pin "7") (pinfunction "VOUT4_7") (pintype "output"))
      (node (ref "U$4") (pin "4") (pinfunction "VOUT1_4") (pintype "bidirectional"))
      (node (ref "U1") (pin "P106") (pinfunction "VCCO_RIGHT2_P106") (pintype "passive"))
      (node (ref "U1") (pin "P115") (pinfunction "VCCO_TOP0_P115") (pintype "passive"))
      (node (ref "U1") (pin "P126") (pinfunction "VCCO_TOP1_P126") (pintype "passive"))
      (node (ref "U1") (pin "P138") (pinfunction "VCCO_TOP2_P138") (pintype "passive"))
      (node (ref "U1") (pin "P19") (pinfunction "VCCO_LEFT1_P19") (pintype "passive"))
      (node (ref "U1") (pin "P3") (pinfunction "VCCO_LEFT0_P3") (pintype "passive"))
      (node (ref "U1") (pin "P34") (pinfunction "VCCO_LEFT2_P34") (pintype "passive"))
      (node (ref "U1") (pin "P43") (pinfunction "VCCO_BOTTOM0_P43") (pintype "passive"))
      (node (ref "U1") (pin "P54") (pinfunction "VCCO_BOTTOM1_P54") (pintype "passive"))
      (node (ref "U1") (pin "P66") (pinfunction "VCCO_BOTTOM2_P66") (pintype "passive"))
      (node (ref "U1") (pin "P75") (pinfunction "VCCO_RIGHT0_P75") (pintype "passive"))
      (node (ref "U1") (pin "P91") (pinfunction "VCCO_RIGHT1_P91") (pintype "passive"))
    )
    (net (code "52") (name "/VCC5") (class "Default")
      (node (ref "R5") (pin "2") (pinfunction "2_2") (pintype "passive"))
      (node (ref "R7") (pin "2") (pinfunction "2_2") (pintype "passive"))
      (node (ref "REG1.2") (pin "3") (pinfunction "VCC_3") (pintype "bidirectional"))
      (node (ref "REG2.5") (pin "3") (pinfunction "VCC_3") (pintype "bidirectional"))
      (node (ref "U$3") (pin "4") (pinfunction "VCC_4") (pintype "bidirectional"))
      (node (ref "U$4") (pin "3") (pinfunction "VCC_3") (pintype "bidirectional"))
      (node (ref "X3") (pin "5") (pinfunction "5_5") (pintype "passive"))
    )
    (net (code "53") (name "/VCCAUX") (class "Default")
      (node (ref "C18") (pin "1") (pinfunction "1_1") (pintype "passive"))
      (node (ref "C19") (pin "1") (pinfunction "1_1") (pintype "passive"))
      (node (ref "C20") (pin "1") (pinfunction "1_1") (pintype "passive"))
      (node (ref "C21") (pin "1") (pinfunction "1_1") (pintype "passive"))
      (node (ref "REG2.5") (pin "2") (pinfunction "VOUT2_2") (pintype "bidirectional"))
      (node (ref "REG2.5") (pin "4") (pinfunction "VOUT1_4") (pintype "bidirectional"))
      (node (ref "U1") (pin "P134") (pinfunction "VCCAUX3_P134") (pintype "passive"))
      (node (ref "U1") (pin "P48") (pinfunction "VCCAUX0_P48") (pintype "passive"))
    )
    (net (code "54") (name "/VCCAUX_R") (class "Default")
      (node (ref "R50") (pin "2") (pinfunction "2_2") (pintype "passive"))
      (node (ref "U1") (pin "P120") (pinfunction "VCCAUX2_P120") (pintype "passive"))
      (node (ref "U1") (pin "P62") (pinfunction "VCCAUX1_P62") (pintype "passive"))
    )
    (net (code "55") (name "/VCCINT") (class "Default")
      (node (ref "C22") (pin "1") (pinfunction "1_1") (pintype "passive"))
      (node (ref "C23") (pin "1") (pinfunction "1_1") (pintype "passive"))
      (node (ref "C24") (pin "1") (pinfunction "1_1") (pintype "passive"))
      (node (ref "C25") (pin "1") (pinfunction "1_1") (pintype "passive"))
      (node (ref "REG1.2") (pin "2") (pinfunction "VOUT2_2") (pintype "bidirectional"))
      (node (ref "REG1.2") (pin "4") (pinfunction "VOUT1_4") (pintype "bidirectional"))
      (node (ref "U1") (pin "P121") (pinfunction "VCCINT2_P121") (pintype "passive"))
      (node (ref "U1") (pin "P133") (pinfunction "VCCINT3_P133") (pintype "passive"))
      (node (ref "U1") (pin "P49") (pinfunction "VCCINT0_P49") (pintype "passive"))
      (node (ref "U1") (pin "P61") (pinfunction "VCCINT1_P61") (pintype "passive"))
    )
    (net (code "56") (name "/VCC_B3") (class "Default")
      (node (ref "R11") (pin "2") (pinfunction "2_2") (pintype "passive"))
    )
    (net (code "57") (name "/X6") (class "Default")
      (node (ref "U1") (pin "P51") (pinfunction "IO_L31N_5D4_P51") (pintype "bidirectional"))
    )
    (net (code "60") (name "/XXCSYNC") (class "Default")
      (node (ref "U1") (pin "P137") (pinfunction "IO_L27N_0_P137") (pintype "bidirectional"))
    )
    (net (code "62") (name "/XXR0") (class "Default")
      (node (ref "U1") (pin "P140") (pinfunction "IO_L01P_0VRN_0_P140") (pintype "bidirectional"))
    )
    (net (code "63") (name "/XXR1") (class "Default")
      (node (ref "U1") (pin "P141") (pinfunction "IO_L01N_0VRP_0_P141") (pintype "bidirectional"))
    )
    (net (code "64") (name "GND") (class "Default")
      (node (ref "C1") (pin "1") (pinfunction "1_1") (pintype "passive"))
      (node (ref "C10") (pin "2") (pinfunction "2_2") (pintype "passive"))
      (node (ref "C11") (pin "2") (pinfunction "2_2") (pintype "passive"))
      (node (ref "C12") (pin "2") (pinfunction "2_2") (pintype "passive"))
      (node (ref "C13") (pin "2") (pinfunction "2_2") (pintype "passive"))
      (node (ref "C14") (pin "2") (pinfunction "2_2") (pintype "passive"))
      (node (ref "C15") (pin "2") (pinfunction "2_2") (pintype "passive"))
      (node (ref "C16") (pin "2") (pinfunction "2_2") (pintype "passive"))
      (node (ref "C17") (pin "2") (pinfunction "2_2") (pintype "passive"))
      (node (ref "C18") (pin "2") (pinfunction "2_2") (pintype "passive"))
      (node (ref "C19") (pin "2") (pinfunction "2_2") (pintype "passive"))
      (node (ref "C20") (pin "2") (pinfunction "2_2") (pintype "passive"))
      (node (ref "C21") (pin "2") (pinfunction "2_2") (pintype "passive"))
      (node (ref "C22") (pin "2") (pinfunction "2_2") (pintype "passive"))
      (node (ref "C23") (pin "2") (pinfunction "2_2") (pintype "passive"))
      (node (ref "C24") (pin "2") (pinfunction "2_2") (pintype "passive"))
      (node (ref "C25") (pin "2") (pinfunction "2_2") (pintype "passive"))
      (node (ref "C5") (pin "1") (pinfunction "1_1") (pintype "passive"))
      (node (ref "C6") (pin "2") (pinfunction "2_2") (pintype "passive"))
      (node (ref "C7") (pin "2") (pinfunction "2_2") (pintype "passive"))
      (node (ref "C8") (pin "2") (pinfunction "2_2") (pintype "passive"))
      (node (ref "C9") (pin "2") (pinfunction "2_2") (pintype "passive"))
      (node (ref "IC1") (pin "11") (pinfunction "GND_11") (pintype "bidirectional"))
      (node (ref "IC2") (pin "4") (pinfunction "GND_4") (pintype "power_in"))
      (node (ref "JP3") (pin "6") (pinfunction "6_6") (pintype "passive"))
      (node (ref "R12") (pin "1") (pinfunction "1_1") (pintype "passive"))
      (node (ref "R17") (pin "1") (pinfunction "1_1") (pintype "passive"))
      (node (ref "R19") (pin "1") (pinfunction "1_1") (pintype "passive"))
      (node (ref "R21") (pin "1") (pinfunction "1_1") (pintype "passive"))
      (node (ref "REG1.2") (pin "1") (pinfunction "GND_1") (pintype "bidirectional"))
      (node (ref "REG2.5") (pin "1") (pinfunction "GND_1") (pintype "bidirectional"))
      (node (ref "RESET_SW") (pin "2") (pinfunction "2_2") (pintype "passive"))
      (node (ref "U$1") (pin "P24") (pinfunction "VSS_P24") (pintype "bidirectional"))
      (node (ref "U$1") (pin "P30") (pinfunction "CE_P30") (pintype "bidirectional"))
      (node (ref "U$2") (pin "GND") (pinfunction "GND_GND") (pintype "power_in"))
      (node (ref "U$3") (pin "1") (pinfunction "GND_1") (pintype "bidirectional"))
      (node (ref "U$4") (pin "1") (pinfunction "GND_1") (pintype "bidirectional"))
      (node (ref "U1") (pin "P101") (pinfunction "GND11_P101") (pintype "passive"))
      (node (ref "U1") (pin "P114") (pinfunction "GND12_P114") (pintype "passive"))
      (node (ref "U1") (pin "P117") (pinfunction "GND13_P117") (pintype "passive"))
      (node (ref "U1") (pin "P136") (pinfunction "GND14_P136") (pintype "passive"))
      (node (ref "U1") (pin "P139") (pinfunction "GND15_P139") (pintype "passive"))
      (node (ref "U1") (pin "P16") (pinfunction "GND1_P16") (pintype "passive"))
      (node (ref "U1") (pin "P22") (pinfunction "GND2_P22") (pintype "passive"))
      (node (ref "U1") (pin "P29") (pinfunction "GND3_P29") (pintype "passive"))
      (node (ref "U1") (pin "P37") (pinfunction "M1_P37") (pintype "bidirectional"))
      (node (ref "U1") (pin "P38") (pinfunction "M0_P38") (pintype "bidirectional"))
      (node (ref "U1") (pin "P39") (pinfunction "M2_P39") (pintype "bidirectional"))
      (node (ref "U1") (pin "P42") (pinfunction "GND4_P42") (pintype "passive"))
      (node (ref "U1") (pin "P45") (pinfunction "GND5_P45") (pintype "passive"))
      (node (ref "U1") (pin "P64") (pinfunction "GND6_P64") (pintype "passive"))
      (node (ref "U1") (pin "P67") (pinfunction "GND7_P67") (pintype "passive"))
      (node (ref "U1") (pin "P81") (pinfunction "GND8_P81") (pintype "passive"))
      (node (ref "U1") (pin "P88") (pinfunction "GND9_P88") (pintype "passive"))
      (node (ref "U1") (pin "P9") (pinfunction "GND0_P9") (pintype "passive"))
      (node (ref "U1") (pin "P94") (pinfunction "GND10_P94") (pintype "passive"))
      (node (ref "X1") (pin "3") (pinfunction "2_3") (pintype "passive"))
      (node (ref "X2") (pin "13") (pinfunction "13_13") (pintype "passive"))
      (node (ref "X2") (pin "14") (pinfunction "14_14") (pintype "passive"))
      (node (ref "X2") (pin "17") (pinfunction "17_17") (pintype "passive"))
      (node (ref "X2") (pin "18") (pinfunction "18_18") (pintype "passive"))
      (node (ref "X2") (pin "21") (pinfunction "21_21") (pintype "passive"))
      (node (ref "X2") (pin "4") (pinfunction "4_4") (pintype "passive"))
      (node (ref "X2") (pin "5") (pinfunction "5_5") (pintype "passive"))
      (node (ref "X2") (pin "9") (pinfunction "9_9") (pintype "passive"))
      (node (ref "X3") (pin "3") (pinfunction "3_3") (pintype "passive"))
      (node (ref "X3") (pin "SH2") (pinfunction "PE2_SH2") (pintype "power_in"))
      (node (ref "X4") (pin "8") (pinfunction "F_8") (pintype "passive"))
      (node (ref "X4") (pin "G1") (pinfunction "G1_G1") (pintype "passive"))
      (node (ref "X5") (pin "8") (pinfunction "F_8") (pintype "passive"))
      (node (ref "X5") (pin "G1") (pinfunction "G1_G1") (pintype "passive"))
    )
    (net (code "65") (name "Net-(C1-Pad2)") (class "Default")
      (node (ref "C1") (pin "2") (pinfunction "2_2") (pintype "passive"))
      (node (ref "R23") (pin "2") (pinfunction "2_2") (pintype "passive"))
      (node (ref "R48") (pin "1") (pinfunction "1_1") (pintype "passive"))
    )
    (net (code "66") (name "Net-(C2-Pad1)") (class "Default")
      (node (ref "C2") (pin "1") (pinfunction "1_1") (pintype "passive"))
      (node (ref "R17") (pin "2") (pinfunction "2_2") (pintype "passive"))
      (node (ref "X1") (pin "1") (pinfunction "1_1") (pintype "passive"))
    )
    (net (code "67") (name "Net-(C3-Pad1)") (class "Default")
      (node (ref "C3") (pin "1") (pinfunction "1_1") (pintype "passive"))
      (node (ref "R48") (pin "2") (pinfunction "2_2") (pintype "passive"))
    )
    (net (code "68") (name "Net-(C4-Pad1)") (class "Default")
      (node (ref "C4") (pin "1") (pinfunction "1_1") (pintype "passive"))
      (node (ref "R49") (pin "2") (pinfunction "2_2") (pintype "passive"))
    )
    (net (code "69") (name "Net-(C5-Pad2)") (class "Default")
      (node (ref "C5") (pin "2") (pinfunction "2_2") (pintype "passive"))
      (node (ref "R34") (pin "2") (pinfunction "2_2") (pintype "passive"))
      (node (ref "R49") (pin "1") (pinfunction "1_1") (pintype "passive"))
    )
    (net (code "70") (name "Net-(IC1-CLK)") (class "Default")
      (node (ref "IC1") (pin "3") (pinfunction "CLK_3") (pintype "bidirectional"))
      (node (ref "U1") (pin "P72") (pinfunction "CCLK_P72") (pintype "bidirectional"))
    )
    (net (code "71") (name "Net-(IC1-TDI)") (class "Default")
      (node (ref "IC1") (pin "4") (pinfunction "TDI_4") (pintype "bidirectional"))
      (node (ref "U1") (pin "P109") (pinfunction "TDO_P109") (pintype "bidirectional"))
    )
    (net (code "72") (name "Net-(IC1-{slash}CE)") (class "Default")
      (node (ref "IC1") (pin "10") (pinfunction "/CE_10") (pintype "bidirectional"))
      (node (ref "U1") (pin "P71") (pinfunction "DONE_P71") (pintype "bidirectional"))
    )
    (net (code "73") (name "Net-(IC1-{slash}CF)") (class "Default")
      (node (ref "IC1") (pin "7") (pinfunction "/CF_7") (pintype "bidirectional"))
      (node (ref "U1") (pin "P143") (pinfunction "PROG_B_P143") (pintype "bidirectional"))
    )
    (net (code "74") (name "Net-(Q5-B)") (class "Default")
      (node (ref "Q5") (pin "1") (pinfunction "B_1") (pintype "passive"))
      (node (ref "R8") (pin "2") (pinfunction "2_2") (pintype "passive"))
    )
    (net (code "75") (name "Net-(Q5-E)") (class "Default")
      (node (ref "Q5") (pin "2") (pinfunction "E_2") (pintype "passive"))
      (node (ref "R13") (pin "2") (pinfunction "2_2") (pintype "passive"))
      (node (ref "R14") (pin "2") (pinfunction "2_2") (pintype "passive"))
    )
    (net (code "76") (name "Net-(Q6-B)") (class "Default")
      (node (ref "Q6") (pin "1") (pinfunction "B_1") (pintype "passive"))
      (node (ref "R10") (pin "2") (pinfunction "2_2") (pintype "passive"))
      (node (ref "R9") (pin "2") (pinfunction "2_2") (pintype "passive"))
    )
    (net (code "77") (name "Net-(Q6-E)") (class "Default")
      (node (ref "Q6") (pin "2") (pinfunction "E_2") (pintype "passive"))
      (node (ref "R15") (pin "2") (pinfunction "2_2") (pintype "passive"))
      (node (ref "R16") (pin "2") (pinfunction "2_2") (pintype "passive"))
      (node (ref "R20") (pin "2") (pinfunction "2_2") (pintype "passive"))
    )
    (net (code "78") (name "Net-(Q7-B)") (class "Default")
      (node (ref "Q7") (pin "1") (pinfunction "B_1") (pintype "passive"))
      (node (ref "R29") (pin "2") (pinfunction "2_2") (pintype "passive"))
      (node (ref "R30") (pin "2") (pinfunction "2_2") (pintype "passive"))
    )
    (net (code "79") (name "Net-(Q7-E)") (class "Default")
      (node (ref "Q7") (pin "2") (pinfunction "E_2") (pintype "passive"))
      (node (ref "R31") (pin "2") (pinfunction "2_2") (pintype "passive"))
      (node (ref "R32") (pin "2") (pinfunction "2_2") (pintype "passive"))
      (node (ref "R33") (pin "2") (pinfunction "2_2") (pintype "passive"))
    )
    (net (code "80") (name "Net-(Q8-B)") (class "Default")
      (node (ref "Q8") (pin "1") (pinfunction "B_1") (pintype "passive"))
      (node (ref "R24") (pin "2") (pinfunction "2_2") (pintype "passive"))
      (node (ref "R25") (pin "2") (pinfunction "2_2") (pintype "passive"))
    )
    (net (code "81") (name "Net-(Q8-E)") (class "Default")
      (node (ref "Q8") (pin "2") (pinfunction "E_2") (pintype "passive"))
      (node (ref "R26") (pin "2") (pinfunction "2_2") (pintype "passive"))
      (node (ref "R27") (pin "2") (pinfunction "2_2") (pintype "passive"))
      (node (ref "R28") (pin "2") (pinfunction "2_2") (pintype "passive"))
    )
    (net (code "82") (name "Net-(R18-Pad2)") (class "Default")
      (node (ref "R18") (pin "2") (pinfunction "2_2") (pintype "passive"))
      (node (ref "R22") (pin "2") (pinfunction "2_2") (pintype "passive"))
    )
    (net (code "83") (name "Net-(T2-B)") (class "Default")
      (node (ref "C2") (pin "2") (pinfunction "2_2") (pintype "passive"))
      (node (ref "R18") (pin "1") (pinfunction "1_1") (pintype "passive"))
      (node (ref "R19") (pin "2") (pinfunction "2_2") (pintype "passive"))
      (node (ref "T2") (pin "1") (pinfunction "B_1") (pintype "passive"))
    )
    (net (code "84") (name "Net-(U$1-A0)") (class "Default")
      (node (ref "U$1") (pin "P20") (pinfunction "A0_P20") (pintype "bidirectional"))
      (node (ref "U1") (pin "P77") (pinfunction "IO_L20P_3_P77") (pintype "bidirectional"))
    )
    (net (code "85") (name "Net-(U$1-A1)") (class "Default")
      (node (ref "U$1") (pin "P19") (pinfunction "A1_P19") (pintype "bidirectional"))
      (node (ref "U1") (pin "P76") (pinfunction "IO_P76") (pintype "bidirectional"))
    )
    (net (code "86") (name "Net-(U$1-A2)") (class "Default")
      (node (ref "U$1") (pin "P18") (pinfunction "A2_P18") (pintype "bidirectional"))
      (node (ref "U1") (pin "P74") (pinfunction "IO_L01N_3VRP_3_P74") (pintype "bidirectional"))
    )
    (net (code "87") (name "Net-(U$1-A3)") (class "Default")
      (node (ref "U$1") (pin "P17") (pinfunction "A3_P17") (pintype "bidirectional"))
      (node (ref "U1") (pin "P73") (pinfunction "IO_L01P_3VRN_3_P73") (pintype "bidirectional"))
    )
    (net (code "88") (name "Net-(U$1-A4)") (class "Default")
      (node (ref "U$1") (pin "P16") (pinfunction "A4_P16") (pintype "bidirectional"))
      (node (ref "U1") (pin "P108") (pinfunction "IO_L01N_2VRP_2_P108") (pintype "bidirectional"))
    )
    (net (code "89") (name "Net-(U$1-A5)") (class "Default")
      (node (ref "U$1") (pin "P15") (pinfunction "A5_P15") (pintype "bidirectional"))
      (node (ref "U1") (pin "P107") (pinfunction "IO_L01P_2VRN_2_P107") (pintype "bidirectional"))
    )
    (net (code "90") (name "Net-(U$1-A6)") (class "Default")
      (node (ref "U$1") (pin "P14") (pinfunction "A6_P14") (pintype "bidirectional"))
      (node (ref "U1") (pin "P105") (pinfunction "IO_L20N_2_P105") (pintype "bidirectional"))
    )
    (net (code "91") (name "Net-(U$1-A7)") (class "Default")
      (node (ref "U$1") (pin "P13") (pinfunction "A7_P13") (pintype "bidirectional"))
      (node (ref "U1") (pin "P104") (pinfunction "IO_L20P_2_P104") (pintype "bidirectional"))
    )
    (net (code "92") (name "Net-(U$1-A8)") (class "Default")
      (node (ref "U$1") (pin "P3") (pinfunction "A8_P3") (pintype "bidirectional"))
      (node (ref "U1") (pin "P93") (pinfunction "IO_L40N_2_P93") (pintype "bidirectional"))
    )
    (net (code "93") (name "Net-(U$1-A9)") (class "Default")
      (node (ref "U$1") (pin "P2") (pinfunction "A9_P2") (pintype "bidirectional"))
      (node (ref "U1") (pin "P92") (pinfunction "IO_L40P_2VREF_2_P92") (pintype "bidirectional"))
    )
    (net (code "94") (name "Net-(U$1-A10)") (class "Default")
      (node (ref "U$1") (pin "P31") (pinfunction "A10_P31") (pintype "bidirectional"))
      (node (ref "U1") (pin "P87") (pinfunction "IO_L24N_3_P87") (pintype "bidirectional"))
    )
    (net (code "95") (name "Net-(U$1-A11)") (class "Default")
      (node (ref "U$1") (pin "P1") (pinfunction "A11_P1") (pintype "bidirectional"))
      (node (ref "U1") (pin "P90") (pinfunction "IO_L40N_3VREF_3_P90") (pintype "bidirectional"))
    )
    (net (code "96") (name "Net-(U$1-A12)") (class "Default")
      (node (ref "U$1") (pin "P12") (pinfunction "A12_P12") (pintype "bidirectional"))
      (node (ref "U1") (pin "P103") (pinfunction "IO_L21N_2_P103") (pintype "bidirectional"))
    )
    (net (code "97") (name "Net-(U$1-A13)") (class "Default")
      (node (ref "U$1") (pin "P4") (pinfunction "A13_P4") (pintype "bidirectional"))
      (node (ref "U1") (pin "P95") (pinfunction "IO_L24P_2_P95") (pintype "bidirectional"))
    )
    (net (code "98") (name "Net-(U$1-A14)") (class "Default")
      (node (ref "U$1") (pin "P11") (pinfunction "A14_P11") (pintype "bidirectional"))
      (node (ref "U1") (pin "P102") (pinfunction "IO_L21P_2_P102") (pintype "bidirectional"))
    )
    (net (code "99") (name "Net-(U$1-A15)") (class "Default")
      (node (ref "U$1") (pin "P7") (pinfunction "A15_P7") (pintype "bidirectional"))
      (node (ref "U1") (pin "P98") (pinfunction "IO_L23N_2VREF_2_P98") (pintype "bidirectional"))
    )
    (net (code "100") (name "Net-(U$1-A16)") (class "Default")
      (node (ref "U$1") (pin "P10") (pinfunction "A16_P10") (pintype "bidirectional"))
      (node (ref "U1") (pin "P100") (pinfunction "IO_L22N_2_P100") (pintype "bidirectional"))
    )
    (net (code "101") (name "Net-(U$1-A17)") (class "Default")
      (node (ref "U$1") (pin "P6") (pinfunction "A17_P6") (pintype "bidirectional"))
      (node (ref "U1") (pin "P97") (pinfunction "IO_L23P_2_P97") (pintype "bidirectional"))
    )
    (net (code "102") (name "Net-(U$1-A18)") (class "Default")
      (node (ref "U$1") (pin "P9") (pinfunction "A18_P9") (pintype "bidirectional"))
      (node (ref "U1") (pin "P99") (pinfunction "IO_L22P_2_P99") (pintype "bidirectional"))
    )
    (net (code "103") (name "Net-(U$1-DQ0)") (class "Default")
      (node (ref "U$1") (pin "P21") (pinfunction "DQ0_P21") (pintype "bidirectional"))
      (node (ref "U1") (pin "P78") (pinfunction "IO_L20N_3_P78") (pintype "bidirectional"))
    )
    (net (code "104") (name "Net-(U$1-DQ1)") (class "Default")
      (node (ref "U$1") (pin "P22") (pinfunction "DQ1_P22") (pintype "bidirectional"))
      (node (ref "U1") (pin "P79") (pinfunction "IO_L21P_3_P79") (pintype "bidirectional"))
    )
    (net (code "105") (name "Net-(U$1-DQ2)") (class "Default")
      (node (ref "U$1") (pin "P23") (pinfunction "DQ2_P23") (pintype "bidirectional"))
      (node (ref "U1") (pin "P80") (pinfunction "IO_L21N_3_P80") (pintype "bidirectional"))
    )
    (net (code "106") (name "Net-(U$1-DQ3)") (class "Default")
      (node (ref "U$1") (pin "P25") (pinfunction "DQ3_P25") (pintype "bidirectional"))
      (node (ref "U1") (pin "P82") (pinfunction "IO_L22P_3_P82") (pintype "bidirectional"))
    )
    (net (code "107") (name "Net-(U$1-DQ4)") (class "Default")
      (node (ref "U$1") (pin "P26") (pinfunction "DQ4_P26") (pintype "bidirectional"))
      (node (ref "U1") (pin "P83") (pinfunction "IO_L22N_3_P83") (pintype "bidirectional"))
    )
    (net (code "108") (name "Net-(U$1-DQ5)") (class "Default")
      (node (ref "U$1") (pin "P27") (pinfunction "DQ5_P27") (pintype "bidirectional"))
      (node (ref "U1") (pin "P84") (pinfunction "IO_L23P_3VREF_3_P84") (pintype "bidirectional"))
    )
    (net (code "109") (name "Net-(U$1-DQ6)") (class "Default")
      (node (ref "U$1") (pin "P28") (pinfunction "DQ6_P28") (pintype "bidirectional"))
      (node (ref "U1") (pin "P85") (pinfunction "IO_L23N_3_P85") (pintype "bidirectional"))
    )
    (net (code "110") (name "Net-(U$1-DQ7)") (class "Default")
      (node (ref "U$1") (pin "P29") (pinfunction "DQ7_P29") (pintype "bidirectional"))
      (node (ref "U1") (pin "P86") (pinfunction "IO_L24P_3_P86") (pintype "bidirectional"))
    )
    (net (code "111") (name "Net-(U$1-OE)") (class "Default")
      (node (ref "U$1") (pin "P32") (pinfunction "OE_P32") (pintype "bidirectional"))
      (node (ref "U1") (pin "P89") (pinfunction "IO_L40P_3_P89") (pintype "bidirectional"))
    )
    (net (code "112") (name "Net-(U$1-WE)") (class "Default")
      (node (ref "U$1") (pin "P5") (pinfunction "WE_P5") (pintype "bidirectional"))
      (node (ref "U1") (pin "P96") (pinfunction "IO_L24N_2_P96") (pintype "bidirectional"))
    )
    (net (code "113") (name "Net-(U1N-TCK)") (class "Default")
      (node (ref "R2") (pin "1") (pinfunction "1_1") (pintype "passive"))
      (node (ref "U1") (pin "P110") (pinfunction "TCK_P110") (pintype "bidirectional"))
    )
    (net (code "114") (name "Net-(U1N-TDI)") (class "Default")
      (node (ref "R1") (pin "1") (pinfunction "1_1") (pintype "passive"))
      (node (ref "U1") (pin "P144") (pinfunction "TDI_P144") (pintype "bidirectional"))
    )
    (net (code "115") (name "Net-(U1N-TMS)") (class "Default")
      (node (ref "R3") (pin "1") (pinfunction "1_1") (pintype "passive"))
      (node (ref "U1") (pin "P111") (pinfunction "TMS_P111") (pintype "bidirectional"))
    )
    (net (code "116") (name "Net-(X4A-F)") (class "Default")
      (node (ref "R40") (pin "2") (pinfunction "2_2") (pintype "passive"))
      (node (ref "X4") (pin "1") (pinfunction "F_1") (pintype "passive"))
    )
    (net (code "117") (name "Net-(X4B-F)") (class "Default")
      (node (ref "R41") (pin "2") (pinfunction "2_2") (pintype "passive"))
      (node (ref "X4") (pin "2") (pinfunction "F_2") (pintype "passive"))
    )
    (net (code "118") (name "Net-(X4C-F)") (class "Default")
      (node (ref "R42") (pin "2") (pinfunction "2_2") (pintype "passive"))
      (node (ref "X4") (pin "3") (pinfunction "F_3") (pintype "passive"))
    )
    (net (code "119") (name "Net-(X4D-F)") (class "Default")
      (node (ref "R43") (pin "2") (pinfunction "2_2") (pintype "passive"))
      (node (ref "X4") (pin "4") (pinfunction "F_4") (pintype "passive"))
    )
    (net (code "120") (name "Net-(X4F-F)") (class "Default")
      (node (ref "R44") (pin "2") (pinfunction "2_2") (pintype "passive"))
      (node (ref "X4") (pin "6") (pinfunction "F_6") (pintype "passive"))
    )
    (net (code "121") (name "Net-(X4G-F)") (class "Default")
      (node (ref "R45") (pin "2") (pinfunction "2_2") (pintype "passive"))
      (node (ref "X4") (pin "7") (pinfunction "F_7") (pintype "passive"))
    )
    (net (code "122") (name "Net-(X5A-F)") (class "Default")
      (node (ref "R46") (pin "1") (pinfunction "1_1") (pintype "passive"))
      (node (ref "X5") (pin "1") (pinfunction "F_1") (pintype "passive"))
    )
    (net (code "123") (name "Net-(X5B-F)") (class "Default")
      (node (ref "R39") (pin "1") (pinfunction "1_1") (pintype "passive"))
      (node (ref "X5") (pin "2") (pinfunction "F_2") (pintype "passive"))
    )
    (net (code "124") (name "Net-(X5C-F)") (class "Default")
      (node (ref "R38") (pin "1") (pinfunction "1_1") (pintype "passive"))
      (node (ref "X5") (pin "3") (pinfunction "F_3") (pintype "passive"))
    )
    (net (code "125") (name "Net-(X5D-F)") (class "Default")
      (node (ref "R37") (pin "1") (pinfunction "1_1") (pintype "passive"))
      (node (ref "X5") (pin "4") (pinfunction "F_4") (pintype "passive"))
    )
    (net (code "126") (name "Net-(X5F-F)") (class "Default")
      (node (ref "R36") (pin "1") (pinfunction "1_1") (pintype "passive"))
      (node (ref "X5") (pin "6") (pinfunction "F_6") (pintype "passive"))
    )
    (net (code "127") (name "Net-(X5G-F)") (class "Default")
      (node (ref "R35") (pin "1") (pinfunction "1_1") (pintype "passive"))
      (node (ref "X5") (pin "7") (pinfunction "F_7") (pintype "passive"))
    )
    (net (code "128") (name "unconnected-(IC1-NC.1-Pad2)") (class "Default")
      (node (ref "IC1") (pin "2") (pinfunction "NC.1_2") (pintype "bidirectional"))
    )
    (net (code "129") (name "unconnected-(IC1-NC.2-Pad9)") (class "Default")
      (node (ref "IC1") (pin "9") (pinfunction "NC.2_9") (pintype "bidirectional"))
    )
    (net (code "130") (name "unconnected-(IC1-NC.3-Pad12)") (class "Default")
      (node (ref "IC1") (pin "12") (pinfunction "NC.3_12") (pintype "bidirectional"))
    )
    (net (code "131") (name "unconnected-(IC1-NC.4-Pad14)") (class "Default")
      (node (ref "IC1") (pin "14") (pinfunction "NC.4_14") (pintype "bidirectional"))
    )
    (net (code "132") (name "unconnected-(IC1-NC.5-Pad15)") (class "Default")
      (node (ref "IC1") (pin "15") (pinfunction "NC.5_15") (pintype "bidirectional"))
    )
    (net (code "133") (name "unconnected-(IC1-NC.6-Pad16)") (class "Default")
      (node (ref "IC1") (pin "16") (pinfunction "NC.6_16") (pintype "bidirectional"))
    )
    (net (code "134") (name "unconnected-(IC1-{slash}CEO-Pad13)") (class "Default")
      (node (ref "IC1") (pin "13") (pinfunction "/CEO_13") (pintype "bidirectional"))
    )
    (net (code "135") (name "unconnected-(IC3-AVCC-Pad32)") (class "Default")
      (node (ref "IC3") (pin "32") (pinfunction "AVCC_32") (pintype "bidirectional"))
    )
    (net (code "136") (name "unconnected-(IC3-D+-Pad29)") (class "Default")
      (node (ref "IC3") (pin "29") (pinfunction "D+_29") (pintype "bidirectional"))
    )
    (net (code "137") (name "unconnected-(IC3-D--Pad30)") (class "Default")
      (node (ref "IC3") (pin "30") (pinfunction "D-_30") (pintype "bidirectional"))
    )
    (net (code "138") (name "unconnected-(IC3-GND-Pad3)") (class "Default")
      (node (ref "IC3") (pin "3") (pinfunction "GND_3") (pintype "bidirectional"))
    )
    (net (code "139") (name "unconnected-(IC3-PC2(AIN2{slash}PCIN11)-Pad5)") (class "Default")
      (node (ref "IC3") (pin "5") (pinfunction "PC2(AIN2/PCIN11)_5") (pintype "bidirectional"))
    )
    (net (code "140") (name "unconnected-(IC3-PC4(PCINT10)-Pad26)") (class "Default")
      (node (ref "IC3") (pin "26") (pinfunction "PC4(PCINT10)_26") (pintype "bidirectional"))
    )
    (net (code "141") (name "unconnected-(IC3-PC5(OC1B{slash}PCINT9)-Pad25)") (class "Default")
      (node (ref "IC3") (pin "25") (pinfunction "PC5(OC1B/PCINT9)_25") (pintype "bidirectional"))
    )
    (net (code "142") (name "unconnected-(IC3-PC6(OC1A{slash}PCINT8)-Pad23)") (class "Default")
      (node (ref "IC3") (pin "23") (pinfunction "PC6(OC1A/PCINT8)_23") (pintype "bidirectional"))
    )
    (net (code "143") (name "unconnected-(IC3-PD0(INT0{slash}OC0B)-Pad6)") (class "Default")
      (node (ref "IC3") (pin "6") (pinfunction "PD0(INT0/OC0B)_6") (pintype "bidirectional"))
    )
    (net (code "144") (name "unconnected-(IC3-PD1(INT1{slash}AIN0)-Pad7)") (class "Default")
      (node (ref "IC3") (pin "7") (pinfunction "PD1(INT1/AIN0)_7") (pintype "bidirectional"))
    )
    (net (code "145") (name "unconnected-(IC3-PD4(INT5{slash}AIN3)-Pad10)") (class "Default")
      (node (ref "IC3") (pin "10") (pinfunction "PD4(INT5/AIN3)_10") (pintype "bidirectional"))
    )
    (net (code "146") (name "unconnected-(IC3-PD5(XCK{slash}AIN4{slash}PCINT12)-Pad11)") (class "Default")
      (node (ref "IC3") (pin "11") (pinfunction "PD5(XCK/AIN4/PCINT12)_11") (pintype "bidirectional"))
    )
    (net (code "147") (name "unconnected-(IC3-PD6(INT6{slash}AIN5{slash}RTS)-Pad12)") (class "Default")
      (node (ref "IC3") (pin "12") (pinfunction "PD6(INT6/AIN5/RTS)_12") (pintype "bidirectional"))
    )
    (net (code "148") (name "unconnected-(IC3-UCAP-Pad27)") (class "Default")
      (node (ref "IC3") (pin "27") (pinfunction "UCAP_27") (pintype "bidirectional"))
    )
    (net (code "149") (name "unconnected-(IC3-UGND-Pad28)") (class "Default")
      (node (ref "IC3") (pin "28") (pinfunction "UGND_28") (pintype "bidirectional"))
    )
    (net (code "150") (name "unconnected-(IC3-UVCC-Pad31)") (class "Default")
      (node (ref "IC3") (pin "31") (pinfunction "UVCC_31") (pintype "bidirectional"))
    )
    (net (code "151") (name "unconnected-(IC3-VCC-Pad4)") (class "Default")
      (node (ref "IC3") (pin "4") (pinfunction "VCC_4") (pintype "bidirectional"))
    )
    (net (code "152") (name "unconnected-(IC3-XTAL1-Pad1)") (class "Default")
      (node (ref "IC3") (pin "1") (pinfunction "XTAL1_1") (pintype "bidirectional"))
    )
    (net (code "153") (name "unconnected-(IC3-XTAL2{slash}PC0-Pad2)") (class "Default")
      (node (ref "IC3") (pin "2") (pinfunction "XTAL2/PC0_2") (pintype "bidirectional"))
    )
    (net (code "154") (name "unconnected-(IC3-{slash}RESET(PC1)-Pad24)") (class "Default")
      (node (ref "IC3") (pin "24") (pinfunction "/RESET(PC1)_24") (pintype "bidirectional"))
    )
    (net (code "155") (name "unconnected-(U$2-TRI-PadENA)") (class "Default")
      (node (ref "U$2") (pin "ENA") (pinfunction "TRI_ENA") (pintype "input"))
    )
    (net (code "156") (name "unconnected-(U$4-VOUT2-Pad2)") (class "Default")
      (node (ref "U$4") (pin "2") (pinfunction "VOUT2_2") (pintype "bidirectional"))
    )
    (net (code "157") (name "unconnected-(U1A-IO_L27P_0-PadP135)") (class "Default")
      (node (ref "U1") (pin "P135") (pinfunction "IO_L27P_0_P135") (pintype "bidirectional"))
    )
    (net (code "158") (name "unconnected-(U1A-IO_L30N_0-PadP132)") (class "Default")
      (node (ref "U1") (pin "P132") (pinfunction "IO_L30N_0_P132") (pintype "bidirectional"))
    )
    (net (code "159") (name "unconnected-(U1A-IO_L30P_0-PadP131)") (class "Default")
      (node (ref "U1") (pin "P131") (pinfunction "IO_L30P_0_P131") (pintype "bidirectional"))
    )
    (net (code "160") (name "unconnected-(U1A-IO_L31N_0-PadP130)") (class "Default")
      (node (ref "U1") (pin "P130") (pinfunction "IO_L31N_0_P130") (pintype "bidirectional"))
    )
    (net (code "161") (name "unconnected-(U1A-IO_L31P_0VREF_0-PadP129)") (class "Default")
      (node (ref "U1") (pin "P129") (pinfunction "IO_L31P_0VREF_0_P129") (pintype "bidirectional"))
    )
    (net (code "162") (name "unconnected-(U1A-IO_L32N_0GCLK7-PadP128)") (class "Default")
      (node (ref "U1") (pin "P128") (pinfunction "IO_L32N_0GCLK7_P128") (pintype "bidirectional"))
    )
    (net (code "163") (name "unconnected-(U1A-IO_L32P_0GCLK6-PadP127)") (class "Default")
      (node (ref "U1") (pin "P127") (pinfunction "IO_L32P_0GCLK6_P127") (pintype "bidirectional"))
    )
    (net (code "164") (name "unconnected-(U1C-IO-PadP116)") (class "Default")
      (node (ref "U1") (pin "P116") (pinfunction "IO_P116") (pintype "bidirectional"))
    )
    (net (code "165") (name "unconnected-(U1C-IO_L01N_1VRP_1-PadP113)") (class "Default")
      (node (ref "U1") (pin "P113") (pinfunction "IO_L01N_1VRP_1_P113") (pintype "bidirectional"))
    )
    (net (code "166") (name "unconnected-(U1C-IO_L01P_1VRN_1-PadP112)") (class "Default")
      (node (ref "U1") (pin "P112") (pinfunction "IO_L01P_1VRN_1_P112") (pintype "bidirectional"))
    )
    (net (code "167") (name "unconnected-(U1C-IO_L28N_1-PadP119)") (class "Default")
      (node (ref "U1") (pin "P119") (pinfunction "IO_L28N_1_P119") (pintype "bidirectional"))
    )
    (net (code "168") (name "unconnected-(U1C-IO_L28P_1-PadP118)") (class "Default")
      (node (ref "U1") (pin "P118") (pinfunction "IO_L28P_1_P118") (pintype "bidirectional"))
    )
    (net (code "169") (name "unconnected-(U1C-IO_L31N_1VREF_1-PadP123)") (class "Default")
      (node (ref "U1") (pin "P123") (pinfunction "IO_L31N_1VREF_1_P123") (pintype "bidirectional"))
    )
    (net (code "170") (name "unconnected-(U1C-IO_L31P_1-PadP122)") (class "Default")
      (node (ref "U1") (pin "P122") (pinfunction "IO_L31P_1_P122") (pintype "bidirectional"))
    )
    (net (code "171") (name "unconnected-(U1C-IO_L32N_1GCLK5-PadP125)") (class "Default")
      (node (ref "U1") (pin "P125") (pinfunction "IO_L32N_1GCLK5_P125") (pintype "bidirectional"))
    )
    (net (code "172") (name "unconnected-(U1C-IO_L32P_1GCLK4-PadP124)") (class "Default")
      (node (ref "U1") (pin "P124") (pinfunction "IO_L32P_1GCLK4_P124") (pintype "bidirectional"))
    )
    (net (code "173") (name "unconnected-(U1J-IO_L01N_6VRP_6-PadP36)") (class "Default")
      (node (ref "U1") (pin "P36") (pinfunction "IO_L01N_6VRP_6_P36") (pintype "bidirectional"))
    )
    (net (code "174") (name "unconnected-(U1J-IO_L01P_6VRN_6-PadP35)") (class "Default")
      (node (ref "U1") (pin "P35") (pinfunction "IO_L01P_6VRN_6_P35") (pintype "bidirectional"))
    )
    (net (code "175") (name "unconnected-(U1J-IO_L20N_6-PadP33)") (class "Default")
      (node (ref "U1") (pin "P33") (pinfunction "IO_L20N_6_P33") (pintype "bidirectional"))
    )
    (net (code "176") (name "unconnected-(U1J-IO_L20P_6-PadP32)") (class "Default")
      (node (ref "U1") (pin "P32") (pinfunction "IO_L20P_6_P32") (pintype "bidirectional"))
    )
    (net (code "177") (name "unconnected-(U1J-IO_L21N_6-PadP31)") (class "Default")
      (node (ref "U1") (pin "P31") (pinfunction "IO_L21N_6_P31") (pintype "bidirectional"))
    )
    (net (code "178") (name "unconnected-(U1J-IO_L21P_6-PadP30)") (class "Default")
      (node (ref "U1") (pin "P30") (pinfunction "IO_L21P_6_P30") (pintype "bidirectional"))
    )
    (net (code "179") (name "unconnected-(U1J-IO_L22N_6-PadP28)") (class "Default")
      (node (ref "U1") (pin "P28") (pinfunction "IO_L22N_6_P28") (pintype "bidirectional"))
    )
    (net (code "180") (name "unconnected-(U1J-IO_L22P_6-PadP27)") (class "Default")
      (node (ref "U1") (pin "P27") (pinfunction "IO_L22P_6_P27") (pintype "bidirectional"))
    )
    (net (code "181") (name "unconnected-(U1J-IO_L23N_6-PadP26)") (class "Default")
      (node (ref "U1") (pin "P26") (pinfunction "IO_L23N_6_P26") (pintype "bidirectional"))
    )
    (net (code "182") (name "unconnected-(U1J-IO_L23P_6-PadP25)") (class "Default")
      (node (ref "U1") (pin "P25") (pinfunction "IO_L23P_6_P25") (pintype "bidirectional"))
    )
    (net (code "183") (name "unconnected-(U1J-IO_L24N_6VREF_6-PadP24)") (class "Default")
      (node (ref "U1") (pin "P24") (pinfunction "IO_L24N_6VREF_6_P24") (pintype "bidirectional"))
    )
    (net (code "184") (name "unconnected-(U1J-IO_L24P_6-PadP23)") (class "Default")
      (node (ref "U1") (pin "P23") (pinfunction "IO_L24P_6_P23") (pintype "bidirectional"))
    )
    (net (code "185") (name "unconnected-(U1J-IO_L40N_6-PadP21)") (class "Default")
      (node (ref "U1") (pin "P21") (pinfunction "IO_L40N_6_P21") (pintype "bidirectional"))
    )
    (net (code "186") (name "unconnected-(U1J-IO_L40P_6VREF_6-PadP20)") (class "Default")
      (node (ref "U1") (pin "P20") (pinfunction "IO_L40P_6VREF_6_P20") (pintype "bidirectional"))
    )
    (net (code "187") (name "unconnected-(U1L-IOVREF_7-PadP4)") (class "Default")
      (node (ref "U1") (pin "P4") (pinfunction "IOVREF_7_P4") (pintype "bidirectional"))
    )
    (net (code "188") (name "unconnected-(U1L-IO_L01N_7VRP_7-PadP2)") (class "Default")
      (node (ref "U1") (pin "P2") (pinfunction "IO_L01N_7VRP_7_P2") (pintype "bidirectional"))
    )
    (net (code "189") (name "unconnected-(U1L-IO_L01P_7VRN_7-PadP1)") (class "Default")
      (node (ref "U1") (pin "P1") (pinfunction "IO_L01P_7VRN_7_P1") (pintype "bidirectional"))
    )
    (net (code "190") (name "unconnected-(U1L-IO_L20N_7-PadP6)") (class "Default")
      (node (ref "U1") (pin "P6") (pinfunction "IO_L20N_7_P6") (pintype "bidirectional"))
    )
    (net (code "191") (name "unconnected-(U1L-IO_L20P_7-PadP5)") (class "Default")
      (node (ref "U1") (pin "P5") (pinfunction "IO_L20P_7_P5") (pintype "bidirectional"))
    )
    (net (code "192") (name "unconnected-(U1L-IO_L21N_7-PadP8)") (class "Default")
      (node (ref "U1") (pin "P8") (pinfunction "IO_L21N_7_P8") (pintype "bidirectional"))
    )
    (net (code "193") (name "unconnected-(U1L-IO_L21P_7-PadP7)") (class "Default")
      (node (ref "U1") (pin "P7") (pinfunction "IO_L21P_7_P7") (pintype "bidirectional"))
    )
    (net (code "194") (name "unconnected-(U1L-IO_L22N_7-PadP11)") (class "Default")
      (node (ref "U1") (pin "P11") (pinfunction "IO_L22N_7_P11") (pintype "bidirectional"))
    )
    (net (code "195") (name "unconnected-(U1L-IO_L22P_7-PadP10)") (class "Default")
      (node (ref "U1") (pin "P10") (pinfunction "IO_L22P_7_P10") (pintype "bidirectional"))
    )
    (net (code "196") (name "unconnected-(U1L-IO_L23N_7-PadP13)") (class "Default")
      (node (ref "U1") (pin "P13") (pinfunction "IO_L23N_7_P13") (pintype "bidirectional"))
    )
    (net (code "197") (name "unconnected-(U1L-IO_L23P_7-PadP12)") (class "Default")
      (node (ref "U1") (pin "P12") (pinfunction "IO_L23P_7_P12") (pintype "bidirectional"))
    )
    (net (code "198") (name "unconnected-(U1L-IO_L24N_7-PadP15)") (class "Default")
      (node (ref "U1") (pin "P15") (pinfunction "IO_L24N_7_P15") (pintype "bidirectional"))
    )
    (net (code "199") (name "unconnected-(U1L-IO_L24P_7-PadP14)") (class "Default")
      (node (ref "U1") (pin "P14") (pinfunction "IO_L24P_7_P14") (pintype "bidirectional"))
    )
    (net (code "200") (name "unconnected-(U1L-IO_L40N_7VREF_7-PadP18)") (class "Default")
      (node (ref "U1") (pin "P18") (pinfunction "IO_L40N_7VREF_7_P18") (pintype "bidirectional"))
    )
    (net (code "201") (name "unconnected-(U1L-IO_L40P_7-PadP17)") (class "Default")
      (node (ref "U1") (pin "P17") (pinfunction "IO_L40P_7_P17") (pintype "bidirectional"))
    )
    (net (code "202") (name "unconnected-(U1N-HSWAP_EN-PadP142)") (class "Default")
      (node (ref "U1") (pin "P142") (pinfunction "HSWAP_EN_P142") (pintype "bidirectional"))
    )
    (net (code "203") (name "unconnected-(X1-3-Pad2)") (class "Default")
      (node (ref "X1") (pin "2") (pinfunction "3_2") (pintype "passive"))
    )
    (net (code "204") (name "unconnected-(X2-Pad10)") (class "Default")
      (node (ref "X2") (pin "10") (pinfunction "10_10") (pintype "passive"))
    )
    (net (code "205") (name "unconnected-(X2-Pad12)") (class "Default")
      (node (ref "X2") (pin "12") (pinfunction "12_12") (pintype "passive"))
    )
    (net (code "206") (name "unconnected-(X3-Pad2)") (class "Default")
      (node (ref "X3") (pin "2") (pinfunction "2_2") (pintype "passive"))
    )
    (net (code "207") (name "unconnected-(X3-Pad8)") (class "Default")
      (node (ref "X3") (pin "8") (pinfunction "8_8") (pintype "passive"))
    )
    (net (code "208") (name "unconnected-(X4-PadG2)") (class "Default")
      (node (ref "X4") (pin "G2") (pinfunction "G2_G2") (pintype "passive"))
    )
    (net (code "209") (name "unconnected-(X5-PadG2)") (class "Default")
      (node (ref "X5") (pin "G2") (pinfunction "G2_G2") (pintype "passive"))
    )
  )
)
